# speaker_amp_single.net
KiCad netlist of a schematic drawn in EAGLE
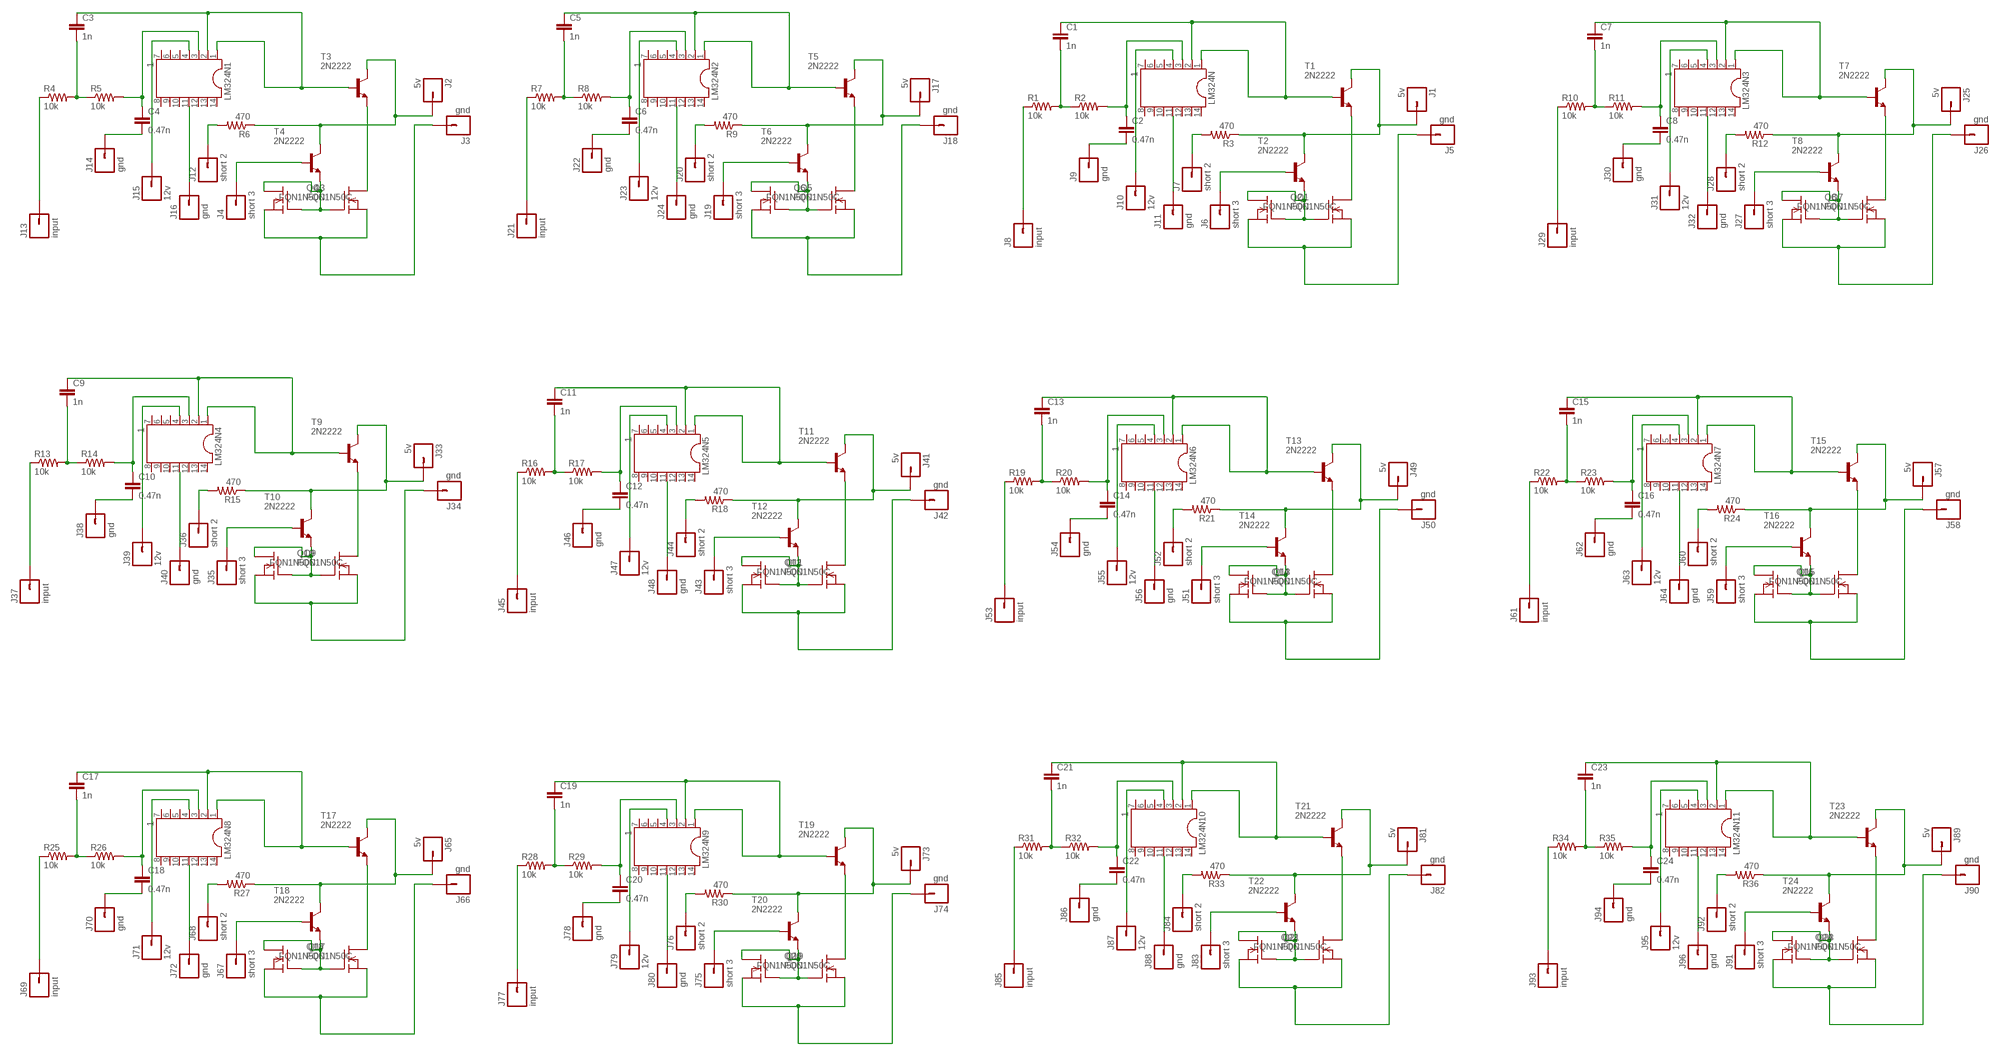
[diagram p0: schematic, sheet 1]

(export (version "E")
  (design (tool "Eeschema 10.0.6"))
  (components
    (comp (ref "C1")
      (value "1n")
      (footprint "eagle-import:CAP-PTH-SMALL")
      (libsource (lib "eagle-import") (part "CAPPTH"))
    )
    (comp (ref "C2")
      (value "0.47n")
      (footprint "eagle-import:CAP-PTH-SMALL")
      (libsource (lib "eagle-import") (part "CAPPTH"))
    )
    (comp (ref "C3")
      (value "1n")
      (footprint "eagle-import:CAP-PTH-SMALL")
      (libsource (lib "eagle-import") (part "CAPPTH"))
    )
    (comp (ref "C4")
      (value "0.47n")
      (footprint "eagle-import:CAP-PTH-SMALL")
      (libsource (lib "eagle-import") (part "CAPPTH"))
    )
    (comp (ref "C5")
      (value "1n")
      (footprint "eagle-import:CAP-PTH-SMALL")
      (libsource (lib "eagle-import") (part "CAPPTH"))
    )
    (comp (ref "C6")
      (value "0.47n")
      (footprint "eagle-import:CAP-PTH-SMALL")
      (libsource (lib "eagle-import") (part "CAPPTH"))
    )
    (comp (ref "C7")
      (value "1n")
      (footprint "eagle-import:CAP-PTH-SMALL")
      (libsource (lib "eagle-import") (part "CAPPTH"))
    )
    (comp (ref "C8")
      (value "0.47n")
      (footprint "eagle-import:CAP-PTH-SMALL")
      (libsource (lib "eagle-import") (part "CAPPTH"))
    )
    (comp (ref "C9")
      (value "1n")
      (footprint "eagle-import:CAP-PTH-SMALL")
      (libsource (lib "eagle-import") (part "CAPPTH"))
    )
    (comp (ref "C10")
      (value "0.47n")
      (footprint "eagle-import:CAP-PTH-SMALL")
      (libsource (lib "eagle-import") (part "CAPPTH"))
    )
    (comp (ref "C11")
      (value "1n")
      (footprint "eagle-import:CAP-PTH-SMALL")
      (libsource (lib "eagle-import") (part "CAPPTH"))
    )
    (comp (ref "C12")
      (value "0.47n")
      (footprint "eagle-import:CAP-PTH-SMALL")
      (libsource (lib "eagle-import") (part "CAPPTH"))
    )
    (comp (ref "C13")
      (value "1n")
      (footprint "eagle-import:CAP-PTH-SMALL")
      (libsource (lib "eagle-import") (part "CAPPTH"))
    )
    (comp (ref "C14")
      (value "0.47n")
      (footprint "eagle-import:CAP-PTH-SMALL")
      (libsource (lib "eagle-import") (part "CAPPTH"))
    )
    (comp (ref "C15")
      (value "1n")
      (footprint "eagle-import:CAP-PTH-SMALL")
      (libsource (lib "eagle-import") (part "CAPPTH"))
    )
    (comp (ref "C16")
      (value "0.47n")
      (footprint "eagle-import:CAP-PTH-SMALL")
      (libsource (lib "eagle-import") (part "CAPPTH"))
    )
    (comp (ref "C17")
      (value "1n")
      (footprint "eagle-import:CAP-PTH-SMALL")
      (libsource (lib "eagle-import") (part "CAPPTH"))
    )
    (comp (ref "C18")
      (value "0.47n")
      (footprint "eagle-import:CAP-PTH-SMALL")
      (libsource (lib "eagle-import") (part "CAPPTH"))
    )
    (comp (ref "C19")
      (value "1n")
      (footprint "eagle-import:CAP-PTH-SMALL")
      (libsource (lib "eagle-import") (part "CAPPTH"))
    )
    (comp (ref "C20")
      (value "0.47n")
      (footprint "eagle-import:CAP-PTH-SMALL")
      (libsource (lib "eagle-import") (part "CAPPTH"))
    )
    (comp (ref "C21")
      (value "1n")
      (footprint "eagle-import:CAP-PTH-SMALL")
      (libsource (lib "eagle-import") (part "CAPPTH"))
    )
    (comp (ref "C22")
      (value "0.47n")
      (footprint "eagle-import:CAP-PTH-SMALL")
      (libsource (lib "eagle-import") (part "CAPPTH"))
    )
    (comp (ref "C23")
      (value "1n")
      (footprint "eagle-import:CAP-PTH-SMALL")
      (libsource (lib "eagle-import") (part "CAPPTH"))
    )
    (comp (ref "C24")
      (value "0.47n")
      (footprint "eagle-import:CAP-PTH-SMALL")
      (libsource (lib "eagle-import") (part "CAPPTH"))
    )
    (comp (ref "J1")
      (value "5v")
      (footprint "eagle-import:1X01")
      (libsource (lib "eagle-import") (part "M01PTH"))
    )
    (comp (ref "J2")
      (value "5v")
      (footprint "eagle-import:1X01")
      (libsource (lib "eagle-import") (part "M01PTH"))
    )
    (comp (ref "J3")
      (value "gnd")
      (footprint "eagle-import:1X01")
      (libsource (lib "eagle-import") (part "M01PTH"))
    )
    (comp (ref "J4")
      (value "short 3")
      (footprint "eagle-import:1X01")
      (libsource (lib "eagle-import") (part "M01PTH"))
    )
    (comp (ref "J5")
      (value "gnd")
      (footprint "eagle-import:1X01")
      (libsource (lib "eagle-import") (part "M01PTH"))
    )
    (comp (ref "J6")
      (value "short 3")
      (footprint "eagle-import:1X01")
      (libsource (lib "eagle-import") (part "M01PTH"))
    )
    (comp (ref "J7")
      (value "short 2")
      (footprint "eagle-import:1X01")
      (libsource (lib "eagle-import") (part "M01PTH"))
    )
    (comp (ref "J8")
      (value "input")
      (footprint "eagle-import:1X01")
      (libsource (lib "eagle-import") (part "M01PTH"))
    )
    (comp (ref "J9")
      (value "gnd")
      (footprint "eagle-import:1X01")
      (libsource (lib "eagle-import") (part "M01PTH"))
    )
    (comp (ref "J10")
      (value "12v")
      (footprint "eagle-import:1X01")
      (libsource (lib "eagle-import") (part "M01PTH"))
    )
    (comp (ref "J11")
      (value "gnd")
      (footprint "eagle-import:1X01")
      (libsource (lib "eagle-import") (part "M01PTH"))
    )
    (comp (ref "J12")
      (value "short 2")
      (footprint "eagle-import:1X01")
      (libsource (lib "eagle-import") (part "M01PTH"))
    )
    (comp (ref "J13")
      (value "input")
      (footprint "eagle-import:1X01")
      (libsource (lib "eagle-import") (part "M01PTH"))
    )
    (comp (ref "J14")
      (value "gnd")
      (footprint "eagle-import:1X01")
      (libsource (lib "eagle-import") (part "M01PTH"))
    )
    (comp (ref "J15")
      (value "12v")
      (footprint "eagle-import:1X01")
      (libsource (lib "eagle-import") (part "M01PTH"))
    )
    (comp (ref "J16")
      (value "gnd")
      (footprint "eagle-import:1X01")
      (libsource (lib "eagle-import") (part "M01PTH"))
    )
    (comp (ref "J17")
      (value "5v")
      (footprint "eagle-import:1X01")
      (libsource (lib "eagle-import") (part "M01PTH"))
    )
    (comp (ref "J18")
      (value "gnd")
      (footprint "eagle-import:1X01")
      (libsource (lib "eagle-import") (part "M01PTH"))
    )
    (comp (ref "J19")
      (value "short 3")
      (footprint "eagle-import:1X01")
      (libsource (lib "eagle-import") (part "M01PTH"))
    )
    (comp (ref "J20")
      (value "short 2")
      (footprint "eagle-import:1X01")
      (libsource (lib "eagle-import") (part "M01PTH"))
    )
    (comp (ref "J21")
      (value "input")
      (footprint "eagle-import:1X01")
      (libsource (lib "eagle-import") (part "M01PTH"))
    )
    (comp (ref "J22")
      (value "gnd")
      (footprint "eagle-import:1X01")
      (libsource (lib "eagle-import") (part "M01PTH"))
    )
    (comp (ref "J23")
      (value "12v")
      (footprint "eagle-import:1X01")
      (libsource (lib "eagle-import") (part "M01PTH"))
    )
    (comp (ref "J24")
      (value "gnd")
      (footprint "eagle-import:1X01")
      (libsource (lib "eagle-import") (part "M01PTH"))
    )
    (comp (ref "J25")
      (value "5v")
      (footprint "eagle-import:1X01")
      (libsource (lib "eagle-import") (part "M01PTH"))
    )
    (comp (ref "J26")
      (value "gnd")
      (footprint "eagle-import:1X01")
      (libsource (lib "eagle-import") (part "M01PTH"))
    )
    (comp (ref "J27")
      (value "short 3")
      (footprint "eagle-import:1X01")
      (libsource (lib "eagle-import") (part "M01PTH"))
    )
    (comp (ref "J28")
      (value "short 2")
      (footprint "eagle-import:1X01")
      (libsource (lib "eagle-import") (part "M01PTH"))
    )
    (comp (ref "J29")
      (value "input")
      (footprint "eagle-import:1X01")
      (libsource (lib "eagle-import") (part "M01PTH"))
    )
    (comp (ref "J30")
      (value "gnd")
      (footprint "eagle-import:1X01")
      (libsource (lib "eagle-import") (part "M01PTH"))
    )
    (comp (ref "J31")
      (value "12v")
      (footprint "eagle-import:1X01")
      (libsource (lib "eagle-import") (part "M01PTH"))
    )
    (comp (ref "J32")
      (value "gnd")
      (footprint "eagle-import:1X01")
      (libsource (lib "eagle-import") (part "M01PTH"))
    )
    (comp (ref "J33")
      (value "5v")
      (footprint "eagle-import:1X01")
      (libsource (lib "eagle-import") (part "M01PTH"))
    )
    (comp (ref "J34")
      (value "gnd")
      (footprint "eagle-import:1X01")
      (libsource (lib "eagle-import") (part "M01PTH"))
    )
    (comp (ref "J35")
      (value "short 3")
      (footprint "eagle-import:1X01")
      (libsource (lib "eagle-import") (part "M01PTH"))
    )
    (comp (ref "J36")
      (value "short 2")
      (footprint "eagle-import:1X01")
      (libsource (lib "eagle-import") (part "M01PTH"))
    )
    (comp (ref "J37")
      (value "input")
      (footprint "eagle-import:1X01")
      (libsource (lib "eagle-import") (part "M01PTH"))
    )
    (comp (ref "J38")
      (value "gnd")
      (footprint "eagle-import:1X01")
      (libsource (lib "eagle-import") (part "M01PTH"))
    )
    (comp (ref "J39")
      (value "12v")
      (footprint "eagle-import:1X01")
      (libsource (lib "eagle-import") (part "M01PTH"))
    )
    (comp (ref "J40")
      (value "gnd")
      (footprint "eagle-import:1X01")
      (libsource (lib "eagle-import") (part "M01PTH"))
    )
    (comp (ref "J41")
      (value "5v")
      (footprint "eagle-import:1X01")
      (libsource (lib "eagle-import") (part "M01PTH"))
    )
    (comp (ref "J42")
      (value "gnd")
      (footprint "eagle-import:1X01")
      (libsource (lib "eagle-import") (part "M01PTH"))
    )
    (comp (ref "J43")
      (value "short 3")
      (footprint "eagle-import:1X01")
      (libsource (lib "eagle-import") (part "M01PTH"))
    )
    (comp (ref "J44")
      (value "short 2")
      (footprint "eagle-import:1X01")
      (libsource (lib "eagle-import") (part "M01PTH"))
    )
    (comp (ref "J45")
      (value "input")
      (footprint "eagle-import:1X01")
      (libsource (lib "eagle-import") (part "M01PTH"))
    )
    (comp (ref "J46")
      (value "gnd")
      (footprint "eagle-import:1X01")
      (libsource (lib "eagle-import") (part "M01PTH"))
    )
    (comp (ref "J47")
      (value "12v")
      (footprint "eagle-import:1X01")
      (libsource (lib "eagle-import") (part "M01PTH"))
    )
    (comp (ref "J48")
      (value "gnd")
      (footprint "eagle-import:1X01")
      (libsource (lib "eagle-import") (part "M01PTH"))
    )
    (comp (ref "J49")
      (value "5v")
      (footprint "eagle-import:1X01")
      (libsource (lib "eagle-import") (part "M01PTH"))
    )
    (comp (ref "J50")
      (value "gnd")
      (footprint "eagle-import:1X01")
      (libsource (lib "eagle-import") (part "M01PTH"))
    )
    (comp (ref "J51")
      (value "short 3")
      (footprint "eagle-import:1X01")
      (libsource (lib "eagle-import") (part "M01PTH"))
    )
    (comp (ref "J52")
      (value "short 2")
      (footprint "eagle-import:1X01")
      (libsource (lib "eagle-import") (part "M01PTH"))
    )
    (comp (ref "J53")
      (value "input")
      (footprint "eagle-import:1X01")
      (libsource (lib "eagle-import") (part "M01PTH"))
    )
    (comp (ref "J54")
      (value "gnd")
      (footprint "eagle-import:1X01")
      (libsource (lib "eagle-import") (part "M01PTH"))
    )
    (comp (ref "J55")
      (value "12v")
      (footprint "eagle-import:1X01")
      (libsource (lib "eagle-import") (part "M01PTH"))
    )
    (comp (ref "J56")
      (value "gnd")
      (footprint "eagle-import:1X01")
      (libsource (lib "eagle-import") (part "M01PTH"))
    )
    (comp (ref "J57")
      (value "5v")
      (footprint "eagle-import:1X01")
      (libsource (lib "eagle-import") (part "M01PTH"))
    )
    (comp (ref "J58")
      (value "gnd")
      (footprint "eagle-import:1X01")
      (libsource (lib "eagle-import") (part "M01PTH"))
    )
    (comp (ref "J59")
      (value "short 3")
      (footprint "eagle-import:1X01")
      (libsource (lib "eagle-import") (part "M01PTH"))
    )
    (comp (ref "J60")
      (value "short 2")
      (footprint "eagle-import:1X01")
      (libsource (lib "eagle-import") (part "M01PTH"))
    )
    (comp (ref "J61")
      (value "input")
      (footprint "eagle-import:1X01")
      (libsource (lib "eagle-import") (part "M01PTH"))
    )
    (comp (ref "J62")
      (value "gnd")
      (footprint "eagle-import:1X01")
      (libsource (lib "eagle-import") (part "M01PTH"))
    )
    (comp (ref "J63")
      (value "12v")
      (footprint "eagle-import:1X01")
      (libsource (lib "eagle-import") (part "M01PTH"))
    )
    (comp (ref "J64")
      (value "gnd")
      (footprint "eagle-import:1X01")
      (libsource (lib "eagle-import") (part "M01PTH"))
    )
    (comp (ref "J65")
      (value "5v")
      (footprint "eagle-import:1X01")
      (libsource (lib "eagle-import") (part "M01PTH"))
    )
    (comp (ref "J66")
      (value "gnd")
      (footprint "eagle-import:1X01")
      (libsource (lib "eagle-import") (part "M01PTH"))
    )
    (comp (ref "J67")
      (value "short 3")
      (footprint "eagle-import:1X01")
      (libsource (lib "eagle-import") (part "M01PTH"))
    )
    (comp (ref "J68")
      (value "short 2")
      (footprint "eagle-import:1X01")
      (libsource (lib "eagle-import") (part "M01PTH"))
    )
    (comp (ref "J69")
      (value "input")
      (footprint "eagle-import:1X01")
      (libsource (lib "eagle-import") (part "M01PTH"))
    )
    (comp (ref "J70")
      (value "gnd")
      (footprint "eagle-import:1X01")
      (libsource (lib "eagle-import") (part "M01PTH"))
    )
    (comp (ref "J71")
      (value "12v")
      (footprint "eagle-import:1X01")
      (libsource (lib "eagle-import") (part "M01PTH"))
    )
    (comp (ref "J72")
      (value "gnd")
      (footprint "eagle-import:1X01")
      (libsource (lib "eagle-import") (part "M01PTH"))
    )
    (comp (ref "J73")
      (value "5v")
      (footprint "eagle-import:1X01")
      (libsource (lib "eagle-import") (part "M01PTH"))
    )
    (comp (ref "J74")
      (value "gnd")
      (footprint "eagle-import:1X01")
      (libsource (lib "eagle-import") (part "M01PTH"))
    )
    (comp (ref "J75")
      (value "short 3")
      (footprint "eagle-import:1X01")
      (libsource (lib "eagle-import") (part "M01PTH"))
    )
    (comp (ref "J76")
      (value "short 2")
      (footprint "eagle-import:1X01")
      (libsource (lib "eagle-import") (part "M01PTH"))
    )
    (comp (ref "J77")
      (value "input")
      (footprint "eagle-import:1X01")
      (libsource (lib "eagle-import") (part "M01PTH"))
    )
    (comp (ref "J78")
      (value "gnd")
      (footprint "eagle-import:1X01")
      (libsource (lib "eagle-import") (part "M01PTH"))
    )
    (comp (ref "J79")
      (value "12v")
      (footprint "eagle-import:1X01")
      (libsource (lib "eagle-import") (part "M01PTH"))
    )
    (comp (ref "J80")
      (value "gnd")
      (footprint "eagle-import:1X01")
      (libsource (lib "eagle-import") (part "M01PTH"))
    )
    (comp (ref "J81")
      (value "5v")
      (footprint "eagle-import:1X01")
      (libsource (lib "eagle-import") (part "M01PTH"))
    )
    (comp (ref "J82")
      (value "gnd")
      (footprint "eagle-import:1X01")
      (libsource (lib "eagle-import") (part "M01PTH"))
    )
    (comp (ref "J83")
      (value "short 3")
      (footprint "eagle-import:1X01")
      (libsource (lib "eagle-import") (part "M01PTH"))
    )
    (comp (ref "J84")
      (value "short 2")
      (footprint "eagle-import:1X01")
      (libsource (lib "eagle-import") (part "M01PTH"))
    )
    (comp (ref "J85")
      (value "input")
      (footprint "eagle-import:1X01")
      (libsource (lib "eagle-import") (part "M01PTH"))
    )
    (comp (ref "J86")
      (value "gnd")
      (footprint "eagle-import:1X01")
      (libsource (lib "eagle-import") (part "M01PTH"))
    )
    (comp (ref "J87")
      (value "12v")
      (footprint "eagle-import:1X01")
      (libsource (lib "eagle-import") (part "M01PTH"))
    )
    (comp (ref "J88")
      (value "gnd")
      (footprint "eagle-import:1X01")
      (libsource (lib "eagle-import") (part "M01PTH"))
    )
    (comp (ref "J89")
      (value "5v")
      (footprint "eagle-import:1X01")
      (libsource (lib "eagle-import") (part "M01PTH"))
    )
    (comp (ref "J90")
      (value "gnd")
      (footprint "eagle-import:1X01")
      (libsource (lib "eagle-import") (part "M01PTH"))
    )
    (comp (ref "J91")
      (value "short 3")
      (footprint "eagle-import:1X01")
      (libsource (lib "eagle-import") (part "M01PTH"))
    )
    (comp (ref "J92")
      (value "short 2")
      (footprint "eagle-import:1X01")
      (libsource (lib "eagle-import") (part "M01PTH"))
    )
    (comp (ref "J93")
      (value "input")
      (footprint "eagle-import:1X01")
      (libsource (lib "eagle-import") (part "M01PTH"))
    )
    (comp (ref "J94")
      (value "gnd")
      (footprint "eagle-import:1X01")
      (libsource (lib "eagle-import") (part "M01PTH"))
    )
    (comp (ref "J95")
      (value "12v")
      (footprint "eagle-import:1X01")
      (libsource (lib "eagle-import") (part "M01PTH"))
    )
    (comp (ref "J96")
      (value "gnd")
      (footprint "eagle-import:1X01")
      (libsource (lib "eagle-import") (part "M01PTH"))
    )
    (comp (ref "LM324N")
      (value "1")
      (footprint "eagle-import:DIL14")
      (libsource (lib "eagle-import") (part "DIL14"))
    )
    (comp (ref "LM324N1")
      (value "1")
      (footprint "eagle-import:DIL14")
      (libsource (lib "eagle-import") (part "DIL14"))
    )
    (comp (ref "LM324N2")
      (value "1")
      (footprint "eagle-import:DIL14")
      (libsource (lib "eagle-import") (part "DIL14"))
    )
    (comp (ref "LM324N3")
      (value "1")
      (footprint "eagle-import:DIL14")
      (libsource (lib "eagle-import") (part "DIL14"))
    )
    (comp (ref "LM324N4")
      (value "1")
      (footprint "eagle-import:DIL14")
      (libsource (lib "eagle-import") (part "DIL14"))
    )
    (comp (ref "LM324N5")
      (value "1")
      (footprint "eagle-import:DIL14")
      (libsource (lib "eagle-import") (part "DIL14"))
    )
    (comp (ref "LM324N6")
      (value "1")
      (footprint "eagle-import:DIL14")
      (libsource (lib "eagle-import") (part "DIL14"))
    )
    (comp (ref "LM324N7")
      (value "1")
      (footprint "eagle-import:DIL14")
      (libsource (lib "eagle-import") (part "DIL14"))
    )
    (comp (ref "LM324N8")
      (value "1")
      (footprint "eagle-import:DIL14")
      (libsource (lib "eagle-import") (part "DIL14"))
    )
    (comp (ref "LM324N9")
      (value "1")
      (footprint "eagle-import:DIL14")
      (libsource (lib "eagle-import") (part "DIL14"))
    )
    (comp (ref "LM324N10")
      (value "1")
      (footprint "eagle-import:DIL14")
      (libsource (lib "eagle-import") (part "DIL14"))
    )
    (comp (ref "LM324N11")
      (value "1")
      (footprint "eagle-import:DIL14")
      (libsource (lib "eagle-import") (part "DIL14"))
    )
    (comp (ref "Q1")
      (value "FQN1N50C")
      (footprint "eagle-import:TO92")
      (libsource (lib "eagle-import") (part "FQN1N50C"))
    )
    (comp (ref "Q2")
      (value "FQN1N50C")
      (footprint "eagle-import:TO92")
      (libsource (lib "eagle-import") (part "FQN1N50C"))
    )
    (comp (ref "Q3")
      (value "FQN1N50C")
      (footprint "eagle-import:TO92")
      (libsource (lib "eagle-import") (part "FQN1N50C"))
    )
    (comp (ref "Q4")
      (value "FQN1N50C")
      (footprint "eagle-import:TO92")
      (libsource (lib "eagle-import") (part "FQN1N50C"))
    )
    (comp (ref "Q5")
      (value "FQN1N50C")
      (footprint "eagle-import:TO92")
      (libsource (lib "eagle-import") (part "FQN1N50C"))
    )
    (comp (ref "Q6")
      (value "FQN1N50C")
      (footprint "eagle-import:TO92")
      (libsource (lib "eagle-import") (part "FQN1N50C"))
    )
    (comp (ref "Q7")
      (value "FQN1N50C")
      (footprint "eagle-import:TO92")
      (libsource (lib "eagle-import") (part "FQN1N50C"))
    )
    (comp (ref "Q8")
      (value "FQN1N50C")
      (footprint "eagle-import:TO92")
      (libsource (lib "eagle-import") (part "FQN1N50C"))
    )
    (comp (ref "Q9")
      (value "FQN1N50C")
      (footprint "eagle-import:TO92")
      (libsource (lib "eagle-import") (part "FQN1N50C"))
    )
    (comp (ref "Q10")
      (value "FQN1N50C")
      (footprint "eagle-import:TO92")
      (libsource (lib "eagle-import") (part "FQN1N50C"))
    )
    (comp (ref "Q11")
      (value "FQN1N50C")
      (footprint "eagle-import:TO92")
      (libsource (lib "eagle-import") (part "FQN1N50C"))
    )
    (comp (ref "Q12")
      (value "FQN1N50C")
      (footprint "eagle-import:TO92")
      (libsource (lib "eagle-import") (part "FQN1N50C"))
    )
    (comp (ref "Q13")
      (value "FQN1N50C")
      (footprint "eagle-import:TO92")
      (libsource (lib "eagle-import") (part "FQN1N50C"))
    )
    (comp (ref "Q14")
      (value "FQN1N50C")
      (footprint "eagle-import:TO92")
      (libsource (lib "eagle-import") (part "FQN1N50C"))
    )
    (comp (ref "Q15")
      (value "FQN1N50C")
      (footprint "eagle-import:TO92")
      (libsource (lib "eagle-import") (part "FQN1N50C"))
    )
    (comp (ref "Q16")
      (value "FQN1N50C")
      (footprint "eagle-import:TO92")
      (libsource (lib "eagle-import") (part "FQN1N50C"))
    )
    (comp (ref "Q17")
      (value "FQN1N50C")
      (footprint "eagle-import:TO92")
      (libsource (lib "eagle-import") (part "FQN1N50C"))
    )
    (comp (ref "Q18")
      (value "FQN1N50C")
      (footprint "eagle-import:TO92")
      (libsource (lib "eagle-import") (part "FQN1N50C"))
    )
    (comp (ref "Q19")
      (value "FQN1N50C")
      (footprint "eagle-import:TO92")
      (libsource (lib "eagle-import") (part "FQN1N50C"))
    )
    (comp (ref "Q20")
      (value "FQN1N50C")
      (footprint "eagle-import:TO92")
      (libsource (lib "eagle-import") (part "FQN1N50C"))
    )
    (comp (ref "Q21")
      (value "FQN1N50C")
      (footprint "eagle-import:TO92")
      (libsource (lib "eagle-import") (part "FQN1N50C"))
    )
    (comp (ref "Q22")
      (value "FQN1N50C")
      (footprint "eagle-import:TO92")
      (libsource (lib "eagle-import") (part "FQN1N50C"))
    )
    (comp (ref "Q23")
      (value "FQN1N50C")
      (footprint "eagle-import:TO92")
      (libsource (lib "eagle-import") (part "FQN1N50C"))
    )
    (comp (ref "Q24")
      (value "FQN1N50C")
      (footprint "eagle-import:TO92")
      (libsource (lib "eagle-import") (part "FQN1N50C"))
    )
    (comp (ref "R1")
      (value "10k")
      (footprint "eagle-import:AXIAL-0.3")
      (libsource (lib "eagle-import") (part "RESISTORAXIAL-0.3"))
    )
    (comp (ref "R2")
      (value "10k")
      (footprint "eagle-import:AXIAL-0.3")
      (libsource (lib "eagle-import") (part "RESISTORAXIAL-0.3"))
    )
    (comp (ref "R3")
      (value "470")
      (footprint "eagle-import:AXIAL-0.3")
      (libsource (lib "eagle-import") (part "RESISTORAXIAL-0.3"))
    )
    (comp (ref "R4")
      (value "10k")
      (footprint "eagle-import:AXIAL-0.3")
      (libsource (lib "eagle-import") (part "RESISTORAXIAL-0.3"))
    )
    (comp (ref "R5")
      (value "10k")
      (footprint "eagle-import:AXIAL-0.3")
      (libsource (lib "eagle-import") (part "RESISTORAXIAL-0.3"))
    )
    (comp (ref "R6")
      (value "470")
      (footprint "eagle-import:AXIAL-0.3")
      (libsource (lib "eagle-import") (part "RESISTORAXIAL-0.3"))
    )
    (comp (ref "R7")
      (value "10k")
      (footprint "eagle-import:AXIAL-0.3")
      (libsource (lib "eagle-import") (part "RESISTORAXIAL-0.3"))
    )
    (comp (ref "R8")
      (value "10k")
      (footprint "eagle-import:AXIAL-0.3")
      (libsource (lib "eagle-import") (part "RESISTORAXIAL-0.3"))
    )
    (comp (ref "R9")
      (value "470")
      (footprint "eagle-import:AXIAL-0.3")
      (libsource (lib "eagle-import") (part "RESISTORAXIAL-0.3"))
    )
    (comp (ref "R10")
      (value "10k")
      (footprint "eagle-import:AXIAL-0.3")
      (libsource (lib "eagle-import") (part "RESISTORAXIAL-0.3"))
    )
    (comp (ref "R11")
      (value "10k")
      (footprint "eagle-import:AXIAL-0.3")
      (libsource (lib "eagle-import") (part "RESISTORAXIAL-0.3"))
    )
    (comp (ref "R12")
      (value "470")
      (footprint "eagle-import:AXIAL-0.3")
      (libsource (lib "eagle-import") (part "RESISTORAXIAL-0.3"))
    )
    (comp (ref "R13")
      (value "10k")
      (footprint "eagle-import:AXIAL-0.3")
      (libsource (lib "eagle-import") (part "RESISTORAXIAL-0.3"))
    )
    (comp (ref "R14")
      (value "10k")
      (footprint "eagle-import:AXIAL-0.3")
      (libsource (lib "eagle-import") (part "RESISTORAXIAL-0.3"))
    )
    (comp (ref "R15")
      (value "470")
      (footprint "eagle-import:AXIAL-0.3")
      (libsource (lib "eagle-import") (part "RESISTORAXIAL-0.3"))
    )
    (comp (ref "R16")
      (value "10k")
      (footprint "eagle-import:AXIAL-0.3")
      (libsource (lib "eagle-import") (part "RESISTORAXIAL-0.3"))
    )
    (comp (ref "R17")
      (value "10k")
      (footprint "eagle-import:AXIAL-0.3")
      (libsource (lib "eagle-import") (part "RESISTORAXIAL-0.3"))
    )
    (comp (ref "R18")
      (value "470")
      (footprint "eagle-import:AXIAL-0.3")
      (libsource (lib "eagle-import") (part "RESISTORAXIAL-0.3"))
    )
    (comp (ref "R19")
      (value "10k")
      (footprint "eagle-import:AXIAL-0.3")
      (libsource (lib "eagle-import") (part "RESISTORAXIAL-0.3"))
    )
    (comp (ref "R20")
      (value "10k")
      (footprint "eagle-import:AXIAL-0.3")
      (libsource (lib "eagle-import") (part "RESISTORAXIAL-0.3"))
    )
    (comp (ref "R21")
      (value "470")
      (footprint "eagle-import:AXIAL-0.3")
      (libsource (lib "eagle-import") (part "RESISTORAXIAL-0.3"))
    )
    (comp (ref "R22")
      (value "10k")
      (footprint "eagle-import:AXIAL-0.3")
      (libsource (lib "eagle-import") (part "RESISTORAXIAL-0.3"))
    )
    (comp (ref "R23")
      (value "10k")
      (footprint "eagle-import:AXIAL-0.3")
      (libsource (lib "eagle-import") (part "RESISTORAXIAL-0.3"))
    )
    (comp (ref "R24")
      (value "470")
      (footprint "eagle-import:AXIAL-0.3")
      (libsource (lib "eagle-import") (part "RESISTORAXIAL-0.3"))
    )
    (comp (ref "R25")
      (value "10k")
      (footprint "eagle-import:AXIAL-0.3")
      (libsource (lib "eagle-import") (part "RESISTORAXIAL-0.3"))
    )
    (comp (ref "R26")
      (value "10k")
      (footprint "eagle-import:AXIAL-0.3")
      (libsource (lib "eagle-import") (part "RESISTORAXIAL-0.3"))
    )
    (comp (ref "R27")
      (value "470")
      (footprint "eagle-import:AXIAL-0.3")
      (libsource (lib "eagle-import") (part "RESISTORAXIAL-0.3"))
    )
    (comp (ref "R28")
      (value "10k")
      (footprint "eagle-import:AXIAL-0.3")
      (libsource (lib "eagle-import") (part "RESISTORAXIAL-0.3"))
    )
    (comp (ref "R29")
      (value "10k")
      (footprint "eagle-import:AXIAL-0.3")
      (libsource (lib "eagle-import") (part "RESISTORAXIAL-0.3"))
    )
    (comp (ref "R30")
      (value "470")
      (footprint "eagle-import:AXIAL-0.3")
      (libsource (lib "eagle-import") (part "RESISTORAXIAL-0.3"))
    )
    (comp (ref "R31")
      (value "10k")
      (footprint "eagle-import:AXIAL-0.3")
      (libsource (lib "eagle-import") (part "RESISTORAXIAL-0.3"))
    )
    (comp (ref "R32")
      (value "10k")
      (footprint "eagle-import:AXIAL-0.3")
      (libsource (lib "eagle-import") (part "RESISTORAXIAL-0.3"))
    )
    (comp (ref "R33")
      (value "470")
      (footprint "eagle-import:AXIAL-0.3")
      (libsource (lib "eagle-import") (part "RESISTORAXIAL-0.3"))
    )
    (comp (ref "R34")
      (value "10k")
      (footprint "eagle-import:AXIAL-0.3")
      (libsource (lib "eagle-import") (part "RESISTORAXIAL-0.3"))
    )
    (comp (ref "R35")
      (value "10k")
      (footprint "eagle-import:AXIAL-0.3")
      (libsource (lib "eagle-import") (part "RESISTORAXIAL-0.3"))
    )
    (comp (ref "R36")
      (value "470")
      (footprint "eagle-import:AXIAL-0.3")
      (libsource (lib "eagle-import") (part "RESISTORAXIAL-0.3"))
    )
    (comp (ref "T1")
      (value "2N2222")
      (footprint "eagle-import:TO92-EBC-OVAL")
      (libsource (lib "eagle-import") (part "2N2222"))
    )
    (comp (ref "T2")
      (value "2N2222")
      (footprint "eagle-import:TO92-EBC-OVAL")
      (libsource (lib "eagle-import") (part "2N2222"))
    )
    (comp (ref "T3")
      (value "2N2222")
      (footprint "eagle-import:TO92-EBC-OVAL")
      (libsource (lib "eagle-import") (part "2N2222"))
    )
    (comp (ref "T4")
      (value "2N2222")
      (footprint "eagle-import:TO92-EBC-OVAL")
      (libsource (lib "eagle-import") (part "2N2222"))
    )
    (comp (ref "T5")
      (value "2N2222")
      (footprint "eagle-import:TO92-EBC-OVAL")
      (libsource (lib "eagle-import") (part "2N2222"))
    )
    (comp (ref "T6")
      (value "2N2222")
      (footprint "eagle-import:TO92-EBC-OVAL")
      (libsource (lib "eagle-import") (part "2N2222"))
    )
    (comp (ref "T7")
      (value "2N2222")
      (footprint "eagle-import:TO92-EBC-OVAL")
      (libsource (lib "eagle-import") (part "2N2222"))
    )
    (comp (ref "T8")
      (value "2N2222")
      (footprint "eagle-import:TO92-EBC-OVAL")
      (libsource (lib "eagle-import") (part "2N2222"))
    )
    (comp (ref "T9")
      (value "2N2222")
      (footprint "eagle-import:TO92-EBC-OVAL")
      (libsource (lib "eagle-import") (part "2N2222"))
    )
    (comp (ref "T10")
      (value "2N2222")
      (footprint "eagle-import:TO92-EBC-OVAL")
      (libsource (lib "eagle-import") (part "2N2222"))
    )
    (comp (ref "T11")
      (value "2N2222")
      (footprint "eagle-import:TO92-EBC-OVAL")
      (libsource (lib "eagle-import") (part "2N2222"))
    )
    (comp (ref "T12")
      (value "2N2222")
      (footprint "eagle-import:TO92-EBC-OVAL")
      (libsource (lib "eagle-import") (part "2N2222"))
    )
    (comp (ref "T13")
      (value "2N2222")
      (footprint "eagle-import:TO92-EBC-OVAL")
      (libsource (lib "eagle-import") (part "2N2222"))
    )
    (comp (ref "T14")
      (value "2N2222")
      (footprint "eagle-import:TO92-EBC-OVAL")
      (libsource (lib "eagle-import") (part "2N2222"))
    )
    (comp (ref "T15")
      (value "2N2222")
      (footprint "eagle-import:TO92-EBC-OVAL")
      (libsource (lib "eagle-import") (part "2N2222"))
    )
    (comp (ref "T16")
      (value "2N2222")
      (footprint "eagle-import:TO92-EBC-OVAL")
      (libsource (lib "eagle-import") (part "2N2222"))
    )
    (comp (ref "T17")
      (value "2N2222")
      (footprint "eagle-import:TO92-EBC-OVAL")
      (libsource (lib "eagle-import") (part "2N2222"))
    )
    (comp (ref "T18")
      (value "2N2222")
      (footprint "eagle-import:TO92-EBC-OVAL")
      (libsource (lib "eagle-import") (part "2N2222"))
    )
    (comp (ref "T19")
      (value "2N2222")
      (footprint "eagle-import:TO92-EBC-OVAL")
      (libsource (lib "eagle-import") (part "2N2222"))
    )
    (comp (ref "T20")
      (value "2N2222")
      (footprint "eagle-import:TO92-EBC-OVAL")
      (libsource (lib "eagle-import") (part "2N2222"))
    )
    (comp (ref "T21")
      (value "2N2222")
      (footprint "eagle-import:TO92-EBC-OVAL")
      (libsource (lib "eagle-import") (part "2N2222"))
    )
    (comp (ref "T22")
      (value "2N2222")
      (footprint "eagle-import:TO92-EBC-OVAL")
      (libsource (lib "eagle-import") (part "2N2222"))
    )
    (comp (ref "T23")
      (value "2N2222")
      (footprint "eagle-import:TO92-EBC-OVAL")
      (libsource (lib "eagle-import") (part "2N2222"))
    )
    (comp (ref "T24")
      (value "2N2222")
      (footprint "eagle-import:TO92-EBC-OVAL")
      (libsource (lib "eagle-import") (part "2N2222"))
    )
  )
  (nets
    (net (code "1") (name "Net-(C1-Pad1)") (class "Default")
      (node (ref "C1") (pin "1") (pinfunction "1_1") (pintype "passive"))
      (node (ref "LM324N") (pin "1") (pinfunction "1_1") (pintype "passive"))
      (node (ref "LM324N") (pin "2") (pinfunction "2_2") (pintype "passive"))
      (node (ref "T1") (pin "B") (pinfunction "B_B") (pintype "passive"))
    )
    (net (code "2") (name "Net-(C2-Pad2)") (class "Default")
      (node (ref "C2") (pin "2") (pinfunction "2_2") (pintype "passive"))
      (node (ref "J9") (pin "1") (pinfunction "1_1") (pintype "passive"))
    )
    (net (code "3") (name "Net-(C3-Pad1)") (class "Default")
      (node (ref "C3") (pin "1") (pinfunction "1_1") (pintype "passive"))
      (node (ref "LM324N1") (pin "1") (pinfunction "1_1") (pintype "passive"))
      (node (ref "LM324N1") (pin "2") (pinfunction "2_2") (pintype "passive"))
      (node (ref "T3") (pin "B") (pinfunction "B_B") (pintype "passive"))
    )
    (net (code "4") (name "Net-(C4-Pad2)") (class "Default")
      (node (ref "C4") (pin "2") (pinfunction "2_2") (pintype "passive"))
      (node (ref "J14") (pin "1") (pinfunction "1_1") (pintype "passive"))
    )
    (net (code "5") (name "Net-(C5-Pad1)") (class "Default")
      (node (ref "C5") (pin "1") (pinfunction "1_1") (pintype "passive"))
      (node (ref "LM324N2") (pin "1") (pinfunction "1_1") (pintype "passive"))
      (node (ref "LM324N2") (pin "2") (pinfunction "2_2") (pintype "passive"))
      (node (ref "T5") (pin "B") (pinfunction "B_B") (pintype "passive"))
    )
    (net (code "6") (name "Net-(C6-Pad2)") (class "Default")
      (node (ref "C6") (pin "2") (pinfunction "2_2") (pintype "passive"))
      (node (ref "J22") (pin "1") (pinfunction "1_1") (pintype "passive"))
    )
    (net (code "7") (name "Net-(C7-Pad1)") (class "Default")
      (node (ref "C7") (pin "1") (pinfunction "1_1") (pintype "passive"))
      (node (ref "LM324N3") (pin "1") (pinfunction "1_1") (pintype "passive"))
      (node (ref "LM324N3") (pin "2") (pinfunction "2_2") (pintype "passive"))
      (node (ref "T7") (pin "B") (pinfunction "B_B") (pintype "passive"))
    )
    (net (code "8") (name "Net-(C8-Pad2)") (class "Default")
      (node (ref "C8") (pin "2") (pinfunction "2_2") (pintype "passive"))
      (node (ref "J30") (pin "1") (pinfunction "1_1") (pintype "passive"))
    )
    (net (code "9") (name "Net-(C9-Pad1)") (class "Default")
      (node (ref "C9") (pin "1") (pinfunction "1_1") (pintype "passive"))
      (node (ref "LM324N4") (pin "1") (pinfunction "1_1") (pintype "passive"))
      (node (ref "LM324N4") (pin "2") (pinfunction "2_2") (pintype "passive"))
      (node (ref "T9") (pin "B") (pinfunction "B_B") (pintype "passive"))
    )
    (net (code "10") (name "Net-(C10-Pad2)") (class "Default")
      (node (ref "C10") (pin "2") (pinfunction "2_2") (pintype "passive"))
      (node (ref "J38") (pin "1") (pinfunction "1_1") (pintype "passive"))
    )
    (net (code "11") (name "Net-(C11-Pad1)") (class "Default")
      (node (ref "C11") (pin "1") (pinfunction "1_1") (pintype "passive"))
      (node (ref "LM324N5") (pin "1") (pinfunction "1_1") (pintype "passive"))
      (node (ref "LM324N5") (pin "2") (pinfunction "2_2") (pintype "passive"))
      (node (ref "T11") (pin "B") (pinfunction "B_B") (pintype "passive"))
    )
    (net (code "12") (name "Net-(C12-Pad2)") (class "Default")
      (node (ref "C12") (pin "2") (pinfunction "2_2") (pintype "passive"))
      (node (ref "J46") (pin "1") (pinfunction "1_1") (pintype "passive"))
    )
    (net (code "13") (name "Net-(C13-Pad1)") (class "Default")
      (node (ref "C13") (pin "1") (pinfunction "1_1") (pintype "passive"))
      (node (ref "LM324N6") (pin "1") (pinfunction "1_1") (pintype "passive"))
      (node (ref "LM324N6") (pin "2") (pinfunction "2_2") (pintype "passive"))
      (node (ref "T13") (pin "B") (pinfunction "B_B") (pintype "passive"))
    )
    (net (code "14") (name "Net-(C14-Pad2)") (class "Default")
      (node (ref "C14") (pin "2") (pinfunction "2_2") (pintype "passive"))
      (node (ref "J54") (pin "1") (pinfunction "1_1") (pintype "passive"))
    )
    (net (code "15") (name "Net-(C15-Pad1)") (class "Default")
      (node (ref "C15") (pin "1") (pinfunction "1_1") (pintype "passive"))
      (node (ref "LM324N7") (pin "1") (pinfunction "1_1") (pintype "passive"))
      (node (ref "LM324N7") (pin "2") (pinfunction "2_2") (pintype "passive"))
      (node (ref "T15") (pin "B") (pinfunction "B_B") (pintype "passive"))
    )
    (net (code "16") (name "Net-(C16-Pad2)") (class "Default")
      (node (ref "C16") (pin "2") (pinfunction "2_2") (pintype "passive"))
      (node (ref "J62") (pin "1") (pinfunction "1_1") (pintype "passive"))
    )
    (net (code "17") (name "Net-(C17-Pad1)") (class "Default")
      (node (ref "C17") (pin "1") (pinfunction "1_1") (pintype "passive"))
      (node (ref "LM324N8") (pin "1") (pinfunction "1_1") (pintype "passive"))
      (node (ref "LM324N8") (pin "2") (pinfunction "2_2") (pintype "passive"))
      (node (ref "T17") (pin "B") (pinfunction "B_B") (pintype "passive"))
    )
    (net (code "18") (name "Net-(C18-Pad2)") (class "Default")
      (node (ref "C18") (pin "2") (pinfunction "2_2") (pintype "passive"))
      (node (ref "J70") (pin "1") (pinfunction "1_1") (pintype "passive"))
    )
    (net (code "19") (name "Net-(C19-Pad1)") (class "Default")
      (node (ref "C19") (pin "1") (pinfunction "1_1") (pintype "passive"))
      (node (ref "LM324N9") (pin "1") (pinfunction "1_1") (pintype "passive"))
      (node (ref "LM324N9") (pin "2") (pinfunction "2_2") (pintype "passive"))
      (node (ref "T19") (pin "B") (pinfunction "B_B") (pintype "passive"))
    )
    (net (code "20") (name "Net-(C20-Pad2)") (class "Default")
      (node (ref "C20") (pin "2") (pinfunction "2_2") (pintype "passive"))
      (node (ref "J78") (pin "1") (pinfunction "1_1") (pintype "passive"))
    )
    (net (code "21") (name "Net-(C21-Pad1)") (class "Default")
      (node (ref "C21") (pin "1") (pinfunction "1_1") (pintype "passive"))
      (node (ref "LM324N10") (pin "1") (pinfunction "1_1") (pintype "passive"))
      (node (ref "LM324N10") (pin "2") (pinfunction "2_2") (pintype "passive"))
      (node (ref "T21") (pin "B") (pinfunction "B_B") (pintype "passive"))
    )
    (net (code "22") (name "Net-(C22-Pad2)") (class "Default")
      (node (ref "C22") (pin "2") (pinfunction "2_2") (pintype "passive"))
      (node (ref "J86") (pin "1") (pinfunction "1_1") (pintype "passive"))
    )
    (net (code "23") (name "Net-(C23-Pad1)") (class "Default")
      (node (ref "C23") (pin "1") (pinfunction "1_1") (pintype "passive"))
      (node (ref "LM324N11") (pin "1") (pinfunction "1_1") (pintype "passive"))
      (node (ref "LM324N11") (pin "2") (pinfunction "2_2") (pintype "passive"))
      (node (ref "T23") (pin "B") (pinfunction "B_B") (pintype "passive"))
    )
    (net (code "24") (name "Net-(C24-Pad2)") (class "Default")
      (node (ref "C24") (pin "2") (pinfunction "2_2") (pintype "passive"))
      (node (ref "J94") (pin "1") (pinfunction "1_1") (pintype "passive"))
    )
    (net (code "25") (name "Net-(J4-Pad1)") (class "Default")
      (node (ref "J4") (pin "1") (pinfunction "1_1") (pintype "passive"))
      (node (ref "T4") (pin "B") (pinfunction "B_B") (pintype "passive"))
    )
    (net (code "26") (name "Net-(J6-Pad1)") (class "Default")
      (node (ref "J6") (pin "1") (pinfunction "1_1") (pintype "passive"))
      (node (ref "T2") (pin "B") (pinfunction "B_B") (pintype "passive"))
    )
    (net (code "27") (name "Net-(J10-Pad1)") (class "Default")
      (node (ref "J10") (pin "1") (pinfunction "1_1") (pintype "passive"))
      (node (ref "LM324N") (pin "4") (pinfunction "4_4") (pintype "passive"))
    )
    (net (code "28") (name "Net-(J11-Pad1)") (class "Default")
      (node (ref "J11") (pin "1") (pinfunction "1_1") (pintype "passive"))
      (node (ref "LM324N") (pin "11") (pinfunction "11_11") (pintype "passive"))
    )
    (net (code "29") (name "Net-(J15-Pad1)") (class "Default")
      (node (ref "J15") (pin "1") (pinfunction "1_1") (pintype "passive"))
      (node (ref "LM324N1") (pin "4") (pinfunction "4_4") (pintype "passive"))
    )
    (net (code "30") (name "Net-(J16-Pad1)") (class "Default")
      (node (ref "J16") (pin "1") (pinfunction "1_1") (pintype "passive"))
      (node (ref "LM324N1") (pin "11") (pinfunction "11_11") (pintype "passive"))
    )
    (net (code "31") (name "Net-(J19-Pad1)") (class "Default")
      (node (ref "J19") (pin "1") (pinfunction "1_1") (pintype "passive"))
      (node (ref "T6") (pin "B") (pinfunction "B_B") (pintype "passive"))
    )
    (net (code "32") (name "Net-(J23-Pad1)") (class "Default")
      (node (ref "J23") (pin "1") (pinfunction "1_1") (pintype "passive"))
      (node (ref "LM324N2") (pin "4") (pinfunction "4_4") (pintype "passive"))
    )
    (net (code "33") (name "Net-(J24-Pad1)") (class "Default")
      (node (ref "J24") (pin "1") (pinfunction "1_1") (pintype "passive"))
      (node (ref "LM324N2") (pin "11") (pinfunction "11_11") (pintype "passive"))
    )
    (net (code "34") (name "Net-(J27-Pad1)") (class "Default")
      (node (ref "J27") (pin "1") (pinfunction "1_1") (pintype "passive"))
      (node (ref "T8") (pin "B") (pinfunction "B_B") (pintype "passive"))
    )
    (net (code "35") (name "Net-(J31-Pad1)") (class "Default")
      (node (ref "J31") (pin "1") (pinfunction "1_1") (pintype "passive"))
      (node (ref "LM324N3") (pin "4") (pinfunction "4_4") (pintype "passive"))
    )
    (net (code "36") (name "Net-(J32-Pad1)") (class "Default")
      (node (ref "J32") (pin "1") (pinfunction "1_1") (pintype "passive"))
      (node (ref "LM324N3") (pin "11") (pinfunction "11_11") (pintype "passive"))
    )
    (net (code "37") (name "Net-(J35-Pad1)") (class "Default")
      (node (ref "J35") (pin "1") (pinfunction "1_1") (pintype "passive"))
      (node (ref "T10") (pin "B") (pinfunction "B_B") (pintype "passive"))
    )
    (net (code "38") (name "Net-(J39-Pad1)") (class "Default")
      (node (ref "J39") (pin "1") (pinfunction "1_1") (pintype "passive"))
      (node (ref "LM324N4") (pin "4") (pinfunction "4_4") (pintype "passive"))
    )
    (net (code "39") (name "Net-(J40-Pad1)") (class "Default")
      (node (ref "J40") (pin "1") (pinfunction "1_1") (pintype "passive"))
      (node (ref "LM324N4") (pin "11") (pinfunction "11_11") (pintype "passive"))
    )
    (net (code "40") (name "Net-(J43-Pad1)") (class "Default")
      (node (ref "J43") (pin "1") (pinfunction "1_1") (pintype "passive"))
      (node (ref "T12") (pin "B") (pinfunction "B_B") (pintype "passive"))
    )
    (net (code "41") (name "Net-(J47-Pad1)") (class "Default")
      (node (ref "J47") (pin "1") (pinfunction "1_1") (pintype "passive"))
      (node (ref "LM324N5") (pin "4") (pinfunction "4_4") (pintype "passive"))
    )
    (net (code "42") (name "Net-(J48-Pad1)") (class "Default")
      (node (ref "J48") (pin "1") (pinfunction "1_1") (pintype "passive"))
      (node (ref "LM324N5") (pin "11") (pinfunction "11_11") (pintype "passive"))
    )
    (net (code "43") (name "Net-(J51-Pad1)") (class "Default")
      (node (ref "J51") (pin "1") (pinfunction "1_1") (pintype "passive"))
      (node (ref "T14") (pin "B") (pinfunction "B_B") (pintype "passive"))
    )
    (net (code "44") (name "Net-(J55-Pad1)") (class "Default")
      (node (ref "J55") (pin "1") (pinfunction "1_1") (pintype "passive"))
      (node (ref "LM324N6") (pin "4") (pinfunction "4_4") (pintype "passive"))
    )
    (net (code "45") (name "Net-(J56-Pad1)") (class "Default")
      (node (ref "J56") (pin "1") (pinfunction "1_1") (pintype "passive"))
      (node (ref "LM324N6") (pin "11") (pinfunction "11_11") (pintype "passive"))
    )
    (net (code "46") (name "Net-(J59-Pad1)") (class "Default")
      (node (ref "J59") (pin "1") (pinfunction "1_1") (pintype "passive"))
      (node (ref "T16") (pin "B") (pinfunction "B_B") (pintype "passive"))
    )
    (net (code "47") (name "Net-(J63-Pad1)") (class "Default")
      (node (ref "J63") (pin "1") (pinfunction "1_1") (pintype "passive"))
      (node (ref "LM324N7") (pin "4") (pinfunction "4_4") (pintype "passive"))
    )
    (net (code "48") (name "Net-(J64-Pad1)") (class "Default")
      (node (ref "J64") (pin "1") (pinfunction "1_1") (pintype "passive"))
      (node (ref "LM324N7") (pin "11") (pinfunction "11_11") (pintype "passive"))
    )
    (net (code "49") (name "Net-(J67-Pad1)") (class "Default")
      (node (ref "J67") (pin "1") (pinfunction "1_1") (pintype "passive"))
      (node (ref "T18") (pin "B") (pinfunction "B_B") (pintype "passive"))
    )
    (net (code "50") (name "Net-(J71-Pad1)") (class "Default")
      (node (ref "J71") (pin "1") (pinfunction "1_1") (pintype "passive"))
      (node (ref "LM324N8") (pin "4") (pinfunction "4_4") (pintype "passive"))
    )
    (net (code "51") (name "Net-(J72-Pad1)") (class "Default")
      (node (ref "J72") (pin "1") (pinfunction "1_1") (pintype "passive"))
      (node (ref "LM324N8") (pin "11") (pinfunction "11_11") (pintype "passive"))
    )
    (net (code "52") (name "Net-(J75-Pad1)") (class "Default")
      (node (ref "J75") (pin "1") (pinfunction "1_1") (pintype "passive"))
      (node (ref "T20") (pin "B") (pinfunction "B_B") (pintype "passive"))
    )
    (net (code "53") (name "Net-(J79-Pad1)") (class "Default")
      (node (ref "J79") (pin "1") (pinfunction "1_1") (pintype "passive"))
      (node (ref "LM324N9") (pin "4") (pinfunction "4_4") (pintype "passive"))
    )
    (net (code "54") (name "Net-(J80-Pad1)") (class "Default")
      (node (ref "J80") (pin "1") (pinfunction "1_1") (pintype "passive"))
      (node (ref "LM324N9") (pin "11") (pinfunction "11_11") (pintype "passive"))
    )
    (net (code "55") (name "Net-(J83-Pad1)") (class "Default")
      (node (ref "J83") (pin "1") (pinfunction "1_1") (pintype "passive"))
      (node (ref "T22") (pin "B") (pinfunction "B_B") (pintype "passive"))
    )
    (net (code "56") (name "Net-(J87-Pad1)") (class "Default")
      (node (ref "J87") (pin "1") (pinfunction "1_1") (pintype "passive"))
      (node (ref "LM324N10") (pin "4") (pinfunction "4_4") (pintype "passive"))
    )
    (net (code "57") (name "Net-(J88-Pad1)") (class "Default")
      (node (ref "J88") (pin "1") (pinfunction "1_1") (pintype "passive"))
      (node (ref "LM324N10") (pin "11") (pinfunction "11_11") (pintype "passive"))
    )
    (net (code "58") (name "Net-(J91-Pad1)") (class "Default")
      (node (ref "J91") (pin "1") (pinfunction "1_1") (pintype "passive"))
      (node (ref "T24") (pin "B") (pinfunction "B_B") (pintype "passive"))
    )
    (net (code "59") (name "Net-(J95-Pad1)") (class "Default")
      (node (ref "J95") (pin "1") (pinfunction "1_1") (pintype "passive"))
      (node (ref "LM324N11") (pin "4") (pinfunction "4_4") (pintype "passive"))
    )
    (net (code "60") (name "Net-(J96-Pad1)") (class "Default")
      (node (ref "J96") (pin "1") (pinfunction "1_1") (pintype "passive"))
      (node (ref "LM324N11") (pin "11") (pinfunction "11_11") (pintype "passive"))
    )
    (net (code "61") (name "Net-(Q1-D)") (class "Default")
      (node (ref "Q1") (pin "1") (pinfunction "G_1") (pintype "passive"))
      (node (ref "Q1") (pin "2") (pinfunction "D_2") (pintype "passive"))
      (node (ref "Q2") (pin "1") (pinfunction "G_1") (pintype "passive"))
      (node (ref "T2") (pin "E") (pinfunction "E_E") (pintype "passive"))
    )
    (net (code "62") (name "Net-(Q1-S)") (class "Default")
      (node (ref "J5") (pin "1") (pinfunction "1_1") (pintype "passive"))
      (node (ref "Q1") (pin "3") (pinfunction "S_3") (pintype "passive"))
      (node (ref "Q2") (pin "3") (pinfunction "S_3") (pintype "passive"))
    )
    (net (code "63") (name "Net-(Q2-D)") (class "Default")
      (node (ref "Q2") (pin "2") (pinfunction "D_2") (pintype "passive"))
      (node (ref "T1") (pin "E") (pinfunction "E_E") (pintype "passive"))
    )
    (net (code "64") (name "Net-(Q3-D)") (class "Default")
      (node (ref "Q3") (pin "1") (pinfunction "G_1") (pintype "passive"))
      (node (ref "Q3") (pin "2") (pinfunction "D_2") (pintype "passive"))
      (node (ref "Q4") (pin "1") (pinfunction "G_1") (pintype "passive"))
      (node (ref "T4") (pin "E") (pinfunction "E_E") (pintype "passive"))
    )
    (net (code "65") (name "Net-(Q3-S)") (class "Default")
      (node (ref "J3") (pin "1") (pinfunction "1_1") (pintype "passive"))
      (node (ref "Q3") (pin "3") (pinfunction "S_3") (pintype "passive"))
      (node (ref "Q4") (pin "3") (pinfunction "S_3") (pintype "passive"))
    )
    (net (code "66") (name "Net-(Q4-D)") (class "Default")
      (node (ref "Q4") (pin "2") (pinfunction "D_2") (pintype "passive"))
      (node (ref "T3") (pin "E") (pinfunction "E_E") (pintype "passive"))
    )
    (net (code "67") (name "Net-(Q5-D)") (class "Default")
      (node (ref "Q5") (pin "1") (pinfunction "G_1") (pintype "passive"))
      (node (ref "Q5") (pin "2") (pinfunction "D_2") (pintype "passive"))
      (node (ref "Q6") (pin "1") (pinfunction "G_1") (pintype "passive"))
      (node (ref "T6") (pin "E") (pinfunction "E_E") (pintype "passive"))
    )
    (net (code "68") (name "Net-(Q5-S)") (class "Default")
      (node (ref "J18") (pin "1") (pinfunction "1_1") (pintype "passive"))
      (node (ref "Q5") (pin "3") (pinfunction "S_3") (pintype "passive"))
      (node (ref "Q6") (pin "3") (pinfunction "S_3") (pintype "passive"))
    )
    (net (code "69") (name "Net-(Q6-D)") (class "Default")
      (node (ref "Q6") (pin "2") (pinfunction "D_2") (pintype "passive"))
      (node (ref "T5") (pin "E") (pinfunction "E_E") (pintype "passive"))
    )
    (net (code "70") (name "Net-(Q7-D)") (class "Default")
      (node (ref "Q7") (pin "1") (pinfunction "G_1") (pintype "passive"))
      (node (ref "Q7") (pin "2") (pinfunction "D_2") (pintype "passive"))
      (node (ref "Q8") (pin "1") (pinfunction "G_1") (pintype "passive"))
      (node (ref "T8") (pin "E") (pinfunction "E_E") (pintype "passive"))
    )
    (net (code "71") (name "Net-(Q7-S)") (class "Default")
      (node (ref "J26") (pin "1") (pinfunction "1_1") (pintype "passive"))
      (node (ref "Q7") (pin "3") (pinfunction "S_3") (pintype "passive"))
      (node (ref "Q8") (pin "3") (pinfunction "S_3") (pintype "passive"))
    )
    (net (code "72") (name "Net-(Q8-D)") (class "Default")
      (node (ref "Q8") (pin "2") (pinfunction "D_2") (pintype "passive"))
      (node (ref "T7") (pin "E") (pinfunction "E_E") (pintype "passive"))
    )
    (net (code "73") (name "Net-(Q10-D)") (class "Default")
      (node (ref "Q10") (pin "2") (pinfunction "D_2") (pintype "passive"))
      (node (ref "T9") (pin "E") (pinfunction "E_E") (pintype "passive"))
    )
    (net (code "74") (name "Net-(Q10-G)") (class "Default")
      (node (ref "Q10") (pin "1") (pinfunction "G_1") (pintype "passive"))
      (node (ref "Q9") (pin "1") (pinfunction "G_1") (pintype "passive"))
      (node (ref "Q9") (pin "2") (pinfunction "D_2") (pintype "passive"))
      (node (ref "T10") (pin "E") (pinfunction "E_E") (pintype "passive"))
    )
    (net (code "75") (name "Net-(Q10-S)") (class "Default")
      (node (ref "J34") (pin "1") (pinfunction "1_1") (pintype "passive"))
      (node (ref "Q10") (pin "3") (pinfunction "S_3") (pintype "passive"))
      (node (ref "Q9") (pin "3") (pinfunction "S_3") (pintype "passive"))
    )
    (net (code "76") (name "Net-(Q11-D)") (class "Default")
      (node (ref "Q11") (pin "1") (pinfunction "G_1") (pintype "passive"))
      (node (ref "Q11") (pin "2") (pinfunction "D_2") (pintype "passive"))
      (node (ref "Q12") (pin "1") (pinfunction "G_1") (pintype "passive"))
      (node (ref "T12") (pin "E") (pinfunction "E_E") (pintype "passive"))
    )
    (net (code "77") (name "Net-(Q11-S)") (class "Default")
      (node (ref "J42") (pin "1") (pinfunction "1_1") (pintype "passive"))
      (node (ref "Q11") (pin "3") (pinfunction "S_3") (pintype "passive"))
      (node (ref "Q12") (pin "3") (pinfunction "S_3") (pintype "passive"))
    )
    (net (code "78") (name "Net-(Q12-D)") (class "Default")
      (node (ref "Q12") (pin "2") (pinfunction "D_2") (pintype "passive"))
      (node (ref "T11") (pin "E") (pinfunction "E_E") (pintype "passive"))
    )
    (net (code "79") (name "Net-(Q13-D)") (class "Default")
      (node (ref "Q13") (pin "1") (pinfunction "G_1") (pintype "passive"))
      (node (ref "Q13") (pin "2") (pinfunction "D_2") (pintype "passive"))
      (node (ref "Q14") (pin "1") (pinfunction "G_1") (pintype "passive"))
      (node (ref "T14") (pin "E") (pinfunction "E_E") (pintype "passive"))
    )
    (net (code "80") (name "Net-(Q13-S)") (class "Default")
      (node (ref "J50") (pin "1") (pinfunction "1_1") (pintype "passive"))
      (node (ref "Q13") (pin "3") (pinfunction "S_3") (pintype "passive"))
      (node (ref "Q14") (pin "3") (pinfunction "S_3") (pintype "passive"))
    )
    (net (code "81") (name "Net-(Q14-D)") (class "Default")
      (node (ref "Q14") (pin "2") (pinfunction "D_2") (pintype "passive"))
      (node (ref "T13") (pin "E") (pinfunction "E_E") (pintype "passive"))
    )
    (net (code "82") (name "Net-(Q15-D)") (class "Default")
      (node (ref "Q15") (pin "1") (pinfunction "G_1") (pintype "passive"))
      (node (ref "Q15") (pin "2") (pinfunction "D_2") (pintype "passive"))
      (node (ref "Q16") (pin "1") (pinfunction "G_1") (pintype "passive"))
      (node (ref "T16") (pin "E") (pinfunction "E_E") (pintype "passive"))
    )
    (net (code "83") (name "Net-(Q15-S)") (class "Default")
      (node (ref "J58") (pin "1") (pinfunction "1_1") (pintype "passive"))
      (node (ref "Q15") (pin "3") (pinfunction "S_3") (pintype "passive"))
      (node (ref "Q16") (pin "3") (pinfunction "S_3") (pintype "passive"))
    )
    (net (code "84") (name "Net-(Q16-D)") (class "Default")
      (node (ref "Q16") (pin "2") (pinfunction "D_2") (pintype "passive"))
      (node (ref "T15") (pin "E") (pinfunction "E_E") (pintype "passive"))
    )
    (net (code "85") (name "Net-(Q17-D)") (class "Default")
      (node (ref "Q17") (pin "1") (pinfunction "G_1") (pintype "passive"))
      (node (ref "Q17") (pin "2") (pinfunction "D_2") (pintype "passive"))
      (node (ref "Q18") (pin "1") (pinfunction "G_1") (pintype "passive"))
      (node (ref "T18") (pin "E") (pinfunction "E_E") (pintype "passive"))
    )
    (net (code "86") (name "Net-(Q17-S)") (class "Default")
      (node (ref "J66") (pin "1") (pinfunction "1_1") (pintype "passive"))
      (node (ref "Q17") (pin "3") (pinfunction "S_3") (pintype "passive"))
      (node (ref "Q18") (pin "3") (pinfunction "S_3") (pintype "passive"))
    )
    (net (code "87") (name "Net-(Q18-D)") (class "Default")
      (node (ref "Q18") (pin "2") (pinfunction "D_2") (pintype "passive"))
      (node (ref "T17") (pin "E") (pinfunction "E_E") (pintype "passive"))
    )
    (net (code "88") (name "Net-(Q19-D)") (class "Default")
      (node (ref "Q19") (pin "1") (pinfunction "G_1") (pintype "passive"))
      (node (ref "Q19") (pin "2") (pinfunction "D_2") (pintype "passive"))
      (node (ref "Q20") (pin "1") (pinfunction "G_1") (pintype "passive"))
      (node (ref "T20") (pin "E") (pinfunction "E_E") (pintype "passive"))
    )
    (net (code "89") (name "Net-(Q19-S)") (class "Default")
      (node (ref "J74") (pin "1") (pinfunction "1_1") (pintype "passive"))
      (node (ref "Q19") (pin "3") (pinfunction "S_3") (pintype "passive"))
      (node (ref "Q20") (pin "3") (pinfunction "S_3") (pintype "passive"))
    )
    (net (code "90") (name "Net-(Q20-D)") (class "Default")
      (node (ref "Q20") (pin "2") (pinfunction "D_2") (pintype "passive"))
      (node (ref "T19") (pin "E") (pinfunction "E_E") (pintype "passive"))
    )
    (net (code "91") (name "Net-(Q21-D)") (class "Default")
      (node (ref "Q21") (pin "1") (pinfunction "G_1") (pintype "passive"))
      (node (ref "Q21") (pin "2") (pinfunction "D_2") (pintype "passive"))
      (node (ref "Q22") (pin "1") (pinfunction "G_1") (pintype "passive"))
      (node (ref "T22") (pin "E") (pinfunction "E_E") (pintype "passive"))
    )
    (net (code "92") (name "Net-(Q21-S)") (class "Default")
      (node (ref "J82") (pin "1") (pinfunction "1_1") (pintype "passive"))
      (node (ref "Q21") (pin "3") (pinfunction "S_3") (pintype "passive"))
      (node (ref "Q22") (pin "3") (pinfunction "S_3") (pintype "passive"))
    )
    (net (code "93") (name "Net-(Q22-D)") (class "Default")
      (node (ref "Q22") (pin "2") (pinfunction "D_2") (pintype "passive"))
      (node (ref "T21") (pin "E") (pinfunction "E_E") (pintype "passive"))
    )
    (net (code "94") (name "Net-(Q23-D)") (class "Default")
      (node (ref "Q23") (pin "1") (pinfunction "G_1") (pintype "passive"))
      (node (ref "Q23") (pin "2") (pinfunction "D_2") (pintype "passive"))
      (node (ref "Q24") (pin "1") (pinfunction "G_1") (pintype "passive"))
      (node (ref "T24") (pin "E") (pinfunction "E_E") (pintype "passive"))
    )
    (net (code "95") (name "Net-(Q23-S)") (class "Default")
      (node (ref "J90") (pin "1") (pinfunction "1_1") (pintype "passive"))
      (node (ref "Q23") (pin "3") (pinfunction "S_3") (pintype "passive"))
      (node (ref "Q24") (pin "3") (pinfunction "S_3") (pintype "passive"))
    )
    (net (code "96") (name "Net-(Q24-D)") (class "Default")
      (node (ref "Q24") (pin "2") (pinfunction "D_2") (pintype "passive"))
      (node (ref "T23") (pin "E") (pinfunction "E_E") (pintype "passive"))
    )
    (net (code "97") (name "Net-(R1-1)") (class "Default")
      (node (ref "J8") (pin "1") (pinfunction "1_1") (pintype "passive"))
      (node (ref "R1") (pin "P$1") (pinfunction "1_P$1") (pintype "passive"))
    )
    (net (code "98") (name "Net-(R1-2)") (class "Default")
      (node (ref "C1") (pin "2") (pinfunction "2_2") (pintype "passive"))
      (node (ref "R1") (pin "P$2") (pinfunction "2_P$2") (pintype "passive"))
      (node (ref "R2") (pin "P$1") (pinfunction "1_P$1") (pintype "passive"))
    )
    (net (code "99") (name "Net-(R2-2)") (class "Default")
      (node (ref "C2") (pin "1") (pinfunction "1_1") (pintype "passive"))
      (node (ref "LM324N") (pin "3") (pinfunction "3_3") (pintype "passive"))
      (node (ref "R2") (pin "P$2") (pinfunction "2_P$2") (pintype "passive"))
    )
    (net (code "100") (name "Net-(R3-1)") (class "Default")
      (node (ref "J1") (pin "1") (pinfunction "1_1") (pintype "passive"))
      (node (ref "R3") (pin "P$1") (pinfunction "1_P$1") (pintype "passive"))
      (node (ref "T1") (pin "C") (pinfunction "C_C") (pintype "passive"))
      (node (ref "T2") (pin "C") (pinfunction "C_C") (pintype "passive"))
    )
    (net (code "101") (name "Net-(R3-2)") (class "Default")
      (node (ref "J7") (pin "1") (pinfunction "1_1") (pintype "passive"))
      (node (ref "R3") (pin "P$2") (pinfunction "2_P$2") (pintype "passive"))
    )
    (net (code "102") (name "Net-(R4-1)") (class "Default")
      (node (ref "J13") (pin "1") (pinfunction "1_1") (pintype "passive"))
      (node (ref "R4") (pin "P$1") (pinfunction "1_P$1") (pintype "passive"))
    )
    (net (code "103") (name "Net-(R4-2)") (class "Default")
      (node (ref "C3") (pin "2") (pinfunction "2_2") (pintype "passive"))
      (node (ref "R4") (pin "P$2") (pinfunction "2_P$2") (pintype "passive"))
      (node (ref "R5") (pin "P$1") (pinfunction "1_P$1") (pintype "passive"))
    )
    (net (code "104") (name "Net-(R5-2)") (class "Default")
      (node (ref "C4") (pin "1") (pinfunction "1_1") (pintype "passive"))
      (node (ref "LM324N1") (pin "3") (pinfunction "3_3") (pintype "passive"))
      (node (ref "R5") (pin "P$2") (pinfunction "2_P$2") (pintype "passive"))
    )
    (net (code "105") (name "Net-(R6-1)") (class "Default")
      (node (ref "J2") (pin "1") (pinfunction "1_1") (pintype "passive"))
      (node (ref "R6") (pin "P$1") (pinfunction "1_P$1") (pintype "passive"))
      (node (ref "T3") (pin "C") (pinfunction "C_C") (pintype "passive"))
      (node (ref "T4") (pin "C") (pinfunction "C_C") (pintype "passive"))
    )
    (net (code "106") (name "Net-(R6-2)") (class "Default")
      (node (ref "J12") (pin "1") (pinfunction "1_1") (pintype "passive"))
      (node (ref "R6") (pin "P$2") (pinfunction "2_P$2") (pintype "passive"))
    )
    (net (code "107") (name "Net-(R7-1)") (class "Default")
      (node (ref "J21") (pin "1") (pinfunction "1_1") (pintype "passive"))
      (node (ref "R7") (pin "P$1") (pinfunction "1_P$1") (pintype "passive"))
    )
    (net (code "108") (name "Net-(R7-2)") (class "Default")
      (node (ref "C5") (pin "2") (pinfunction "2_2") (pintype "passive"))
      (node (ref "R7") (pin "P$2") (pinfunction "2_P$2") (pintype "passive"))
      (node (ref "R8") (pin "P$1") (pinfunction "1_P$1") (pintype "passive"))
    )
    (net (code "109") (name "Net-(R8-2)") (class "Default")
      (node (ref "C6") (pin "1") (pinfunction "1_1") (pintype "passive"))
      (node (ref "LM324N2") (pin "3") (pinfunction "3_3") (pintype "passive"))
      (node (ref "R8") (pin "P$2") (pinfunction "2_P$2") (pintype "passive"))
    )
    (net (code "110") (name "Net-(R9-1)") (class "Default")
      (node (ref "J17") (pin "1") (pinfunction "1_1") (pintype "passive"))
      (node (ref "R9") (pin "P$1") (pinfunction "1_P$1") (pintype "passive"))
      (node (ref "T5") (pin "C") (pinfunction "C_C") (pintype "passive"))
      (node (ref "T6") (pin "C") (pinfunction "C_C") (pintype "passive"))
    )
    (net (code "111") (name "Net-(R9-2)") (class "Default")
      (node (ref "J20") (pin "1") (pinfunction "1_1") (pintype "passive"))
      (node (ref "R9") (pin "P$2") (pinfunction "2_P$2") (pintype "passive"))
    )
    (net (code "112") (name "Net-(R10-1)") (class "Default")
      (node (ref "J29") (pin "1") (pinfunction "1_1") (pintype "passive"))
      (node (ref "R10") (pin "P$1") (pinfunction "1_P$1") (pintype "passive"))
    )
    (net (code "113") (name "Net-(R10-2)") (class "Default")
      (node (ref "C7") (pin "2") (pinfunction "2_2") (pintype "passive"))
      (node (ref "R10") (pin "P$2") (pinfunction "2_P$2") (pintype "passive"))
      (node (ref "R11") (pin "P$1") (pinfunction "1_P$1") (pintype "passive"))
    )
    (net (code "114") (name "Net-(R11-2)") (class "Default")
      (node (ref "C8") (pin "1") (pinfunction "1_1") (pintype "passive"))
      (node (ref "LM324N3") (pin "3") (pinfunction "3_3") (pintype "passive"))
      (node (ref "R11") (pin "P$2") (pinfunction "2_P$2") (pintype "passive"))
    )
    (net (code "115") (name "Net-(R12-1)") (class "Default")
      (node (ref "J25") (pin "1") (pinfunction "1_1") (pintype "passive"))
      (node (ref "R12") (pin "P$1") (pinfunction "1_P$1") (pintype "passive"))
      (node (ref "T7") (pin "C") (pinfunction "C_C") (pintype "passive"))
      (node (ref "T8") (pin "C") (pinfunction "C_C") (pintype "passive"))
    )
    (net (code "116") (name "Net-(R12-2)") (class "Default")
      (node (ref "J28") (pin "1") (pinfunction "1_1") (pintype "passive"))
      (node (ref "R12") (pin "P$2") (pinfunction "2_P$2") (pintype "passive"))
    )
    (net (code "117") (name "Net-(R13-1)") (class "Default")
      (node (ref "J37") (pin "1") (pinfunction "1_1") (pintype "passive"))
      (node (ref "R13") (pin "P$1") (pinfunction "1_P$1") (pintype "passive"))
    )
    (net (code "118") (name "Net-(R13-2)") (class "Default")
      (node (ref "C9") (pin "2") (pinfunction "2_2") (pintype "passive"))
      (node (ref "R13") (pin "P$2") (pinfunction "2_P$2") (pintype "passive"))
      (node (ref "R14") (pin "P$1") (pinfunction "1_P$1") (pintype "passive"))
    )
    (net (code "119") (name "Net-(R14-2)") (class "Default")
      (node (ref "C10") (pin "1") (pinfunction "1_1") (pintype "passive"))
      (node (ref "LM324N4") (pin "3") (pinfunction "3_3") (pintype "passive"))
      (node (ref "R14") (pin "P$2") (pinfunction "2_P$2") (pintype "passive"))
    )
    (net (code "120") (name "Net-(R15-1)") (class "Default")
      (node (ref "J33") (pin "1") (pinfunction "1_1") (pintype "passive"))
      (node (ref "R15") (pin "P$1") (pinfunction "1_P$1") (pintype "passive"))
      (node (ref "T10") (pin "C") (pinfunction "C_C") (pintype "passive"))
      (node (ref "T9") (pin "C") (pinfunction "C_C") (pintype "passive"))
    )
    (net (code "121") (name "Net-(R15-2)") (class "Default")
      (node (ref "J36") (pin "1") (pinfunction "1_1") (pintype "passive"))
      (node (ref "R15") (pin "P$2") (pinfunction "2_P$2") (pintype "passive"))
    )
    (net (code "122") (name "Net-(R16-1)") (class "Default")
      (node (ref "J45") (pin "1") (pinfunction "1_1") (pintype "passive"))
      (node (ref "R16") (pin "P$1") (pinfunction "1_P$1") (pintype "passive"))
    )
    (net (code "123") (name "Net-(R16-2)") (class "Default")
      (node (ref "C11") (pin "2") (pinfunction "2_2") (pintype "passive"))
      (node (ref "R16") (pin "P$2") (pinfunction "2_P$2") (pintype "passive"))
      (node (ref "R17") (pin "P$1") (pinfunction "1_P$1") (pintype "passive"))
    )
    (net (code "124") (name "Net-(R17-2)") (class "Default")
      (node (ref "C12") (pin "1") (pinfunction "1_1") (pintype "passive"))
      (node (ref "LM324N5") (pin "3") (pinfunction "3_3") (pintype "passive"))
      (node (ref "R17") (pin "P$2") (pinfunction "2_P$2") (pintype "passive"))
    )
    (net (code "125") (name "Net-(R18-1)") (class "Default")
      (node (ref "J41") (pin "1") (pinfunction "1_1") (pintype "passive"))
      (node (ref "R18") (pin "P$1") (pinfunction "1_P$1") (pintype "passive"))
      (node (ref "T11") (pin "C") (pinfunction "C_C") (pintype "passive"))
      (node (ref "T12") (pin "C") (pinfunction "C_C") (pintype "passive"))
    )
    (net (code "126") (name "Net-(R18-2)") (class "Default")
      (node (ref "J44") (pin "1") (pinfunction "1_1") (pintype "passive"))
      (node (ref "R18") (pin "P$2") (pinfunction "2_P$2") (pintype "passive"))
    )
    (net (code "127") (name "Net-(R19-1)") (class "Default")
      (node (ref "J53") (pin "1") (pinfunction "1_1") (pintype "passive"))
      (node (ref "R19") (pin "P$1") (pinfunction "1_P$1") (pintype "passive"))
    )
    (net (code "128") (name "Net-(R19-2)") (class "Default")
      (node (ref "C13") (pin "2") (pinfunction "2_2") (pintype "passive"))
      (node (ref "R19") (pin "P$2") (pinfunction "2_P$2") (pintype "passive"))
      (node (ref "R20") (pin "P$1") (pinfunction "1_P$1") (pintype "passive"))
    )
    (net (code "129") (name "Net-(R20-2)") (class "Default")
      (node (ref "C14") (pin "1") (pinfunction "1_1") (pintype "passive"))
      (node (ref "LM324N6") (pin "3") (pinfunction "3_3") (pintype "passive"))
      (node (ref "R20") (pin "P$2") (pinfunction "2_P$2") (pintype "passive"))
    )
    (net (code "130") (name "Net-(R21-1)") (class "Default")
      (node (ref "J49") (pin "1") (pinfunction "1_1") (pintype "passive"))
      (node (ref "R21") (pin "P$1") (pinfunction "1_P$1") (pintype "passive"))
      (node (ref "T13") (pin "C") (pinfunction "C_C") (pintype "passive"))
      (node (ref "T14") (pin "C") (pinfunction "C_C") (pintype "passive"))
    )
    (net (code "131") (name "Net-(R21-2)") (class "Default")
      (node (ref "J52") (pin "1") (pinfunction "1_1") (pintype "passive"))
      (node (ref "R21") (pin "P$2") (pinfunction "2_P$2") (pintype "passive"))
    )
    (net (code "132") (name "Net-(R22-1)") (class "Default")
      (node (ref "J61") (pin "1") (pinfunction "1_1") (pintype "passive"))
      (node (ref "R22") (pin "P$1") (pinfunction "1_P$1") (pintype "passive"))
    )
    (net (code "133") (name "Net-(R22-2)") (class "Default")
      (node (ref "C15") (pin "2") (pinfunction "2_2") (pintype "passive"))
      (node (ref "R22") (pin "P$2") (pinfunction "2_P$2") (pintype "passive"))
      (node (ref "R23") (pin "P$1") (pinfunction "1_P$1") (pintype "passive"))
    )
    (net (code "134") (name "Net-(R23-2)") (class "Default")
      (node (ref "C16") (pin "1") (pinfunction "1_1") (pintype "passive"))
      (node (ref "LM324N7") (pin "3") (pinfunction "3_3") (pintype "passive"))
      (node (ref "R23") (pin "P$2") (pinfunction "2_P$2") (pintype "passive"))
    )
    (net (code "135") (name "Net-(R24-1)") (class "Default")
      (node (ref "J57") (pin "1") (pinfunction "1_1") (pintype "passive"))
      (node (ref "R24") (pin "P$1") (pinfunction "1_P$1") (pintype "passive"))
      (node (ref "T15") (pin "C") (pinfunction "C_C") (pintype "passive"))
      (node (ref "T16") (pin "C") (pinfunction "C_C") (pintype "passive"))
    )
    (net (code "136") (name "Net-(R24-2)") (class "Default")
      (node (ref "J60") (pin "1") (pinfunction "1_1") (pintype "passive"))
      (node (ref "R24") (pin "P$2") (pinfunction "2_P$2") (pintype "passive"))
    )
    (net (code "137") (name "Net-(R25-1)") (class "Default")
      (node (ref "J69") (pin "1") (pinfunction "1_1") (pintype "passive"))
      (node (ref "R25") (pin "P$1") (pinfunction "1_P$1") (pintype "passive"))
    )
    (net (code "138") (name "Net-(R25-2)") (class "Default")
      (node (ref "C17") (pin "2") (pinfunction "2_2") (pintype "passive"))
      (node (ref "R25") (pin "P$2") (pinfunction "2_P$2") (pintype "passive"))
      (node (ref "R26") (pin "P$1") (pinfunction "1_P$1") (pintype "passive"))
    )
    (net (code "139") (name "Net-(R26-2)") (class "Default")
      (node (ref "C18") (pin "1") (pinfunction "1_1") (pintype "passive"))
      (node (ref "LM324N8") (pin "3") (pinfunction "3_3") (pintype "passive"))
      (node (ref "R26") (pin "P$2") (pinfunction "2_P$2") (pintype "passive"))
    )
    (net (code "140") (name "Net-(R27-1)") (class "Default")
      (node (ref "J65") (pin "1") (pinfunction "1_1") (pintype "passive"))
      (node (ref "R27") (pin "P$1") (pinfunction "1_P$1") (pintype "passive"))
      (node (ref "T17") (pin "C") (pinfunction "C_C") (pintype "passive"))
      (node (ref "T18") (pin "C") (pinfunction "C_C") (pintype "passive"))
    )
    (net (code "141") (name "Net-(R27-2)") (class "Default")
      (node (ref "J68") (pin "1") (pinfunction "1_1") (pintype "passive"))
      (node (ref "R27") (pin "P$2") (pinfunction "2_P$2") (pintype "passive"))
    )
    (net (code "142") (name "Net-(R28-1)") (class "Default")
      (node (ref "J77") (pin "1") (pinfunction "1_1") (pintype "passive"))
      (node (ref "R28") (pin "P$1") (pinfunction "1_P$1") (pintype "passive"))
    )
    (net (code "143") (name "Net-(R28-2)") (class "Default")
      (node (ref "C19") (pin "2") (pinfunction "2_2") (pintype "passive"))
      (node (ref "R28") (pin "P$2") (pinfunction "2_P$2") (pintype "passive"))
      (node (ref "R29") (pin "P$1") (pinfunction "1_P$1") (pintype "passive"))
    )
    (net (code "144") (name "Net-(R29-2)") (class "Default")
      (node (ref "C20") (pin "1") (pinfunction "1_1") (pintype "passive"))
      (node (ref "LM324N9") (pin "3") (pinfunction "3_3") (pintype "passive"))
      (node (ref "R29") (pin "P$2") (pinfunction "2_P$2") (pintype "passive"))
    )
    (net (code "145") (name "Net-(R30-1)") (class "Default")
      (node (ref "J73") (pin "1") (pinfunction "1_1") (pintype "passive"))
      (node (ref "R30") (pin "P$1") (pinfunction "1_P$1") (pintype "passive"))
      (node (ref "T19") (pin "C") (pinfunction "C_C") (pintype "passive"))
      (node (ref "T20") (pin "C") (pinfunction "C_C") (pintype "passive"))
    )
    (net (code "146") (name "Net-(R30-2)") (class "Default")
      (node (ref "J76") (pin "1") (pinfunction "1_1") (pintype "passive"))
      (node (ref "R30") (pin "P$2") (pinfunction "2_P$2") (pintype "passive"))
    )
    (net (code "147") (name "Net-(R31-1)") (class "Default")
      (node (ref "J85") (pin "1") (pinfunction "1_1") (pintype "passive"))
      (node (ref "R31") (pin "P$1") (pinfunction "1_P$1") (pintype "passive"))
    )
    (net (code "148") (name "Net-(R31-2)") (class "Default")
      (node (ref "C21") (pin "2") (pinfunction "2_2") (pintype "passive"))
      (node (ref "R31") (pin "P$2") (pinfunction "2_P$2") (pintype "passive"))
      (node (ref "R32") (pin "P$1") (pinfunction "1_P$1") (pintype "passive"))
    )
    (net (code "149") (name "Net-(R32-2)") (class "Default")
      (node (ref "C22") (pin "1") (pinfunction "1_1") (pintype "passive"))
      (node (ref "LM324N10") (pin "3") (pinfunction "3_3") (pintype "passive"))
      (node (ref "R32") (pin "P$2") (pinfunction "2_P$2") (pintype "passive"))
    )
    (net (code "150") (name "Net-(R33-1)") (class "Default")
      (node (ref "J81") (pin "1") (pinfunction "1_1") (pintype "passive"))
      (node (ref "R33") (pin "P$1") (pinfunction "1_P$1") (pintype "passive"))
      (node (ref "T21") (pin "C") (pinfunction "C_C") (pintype "passive"))
      (node (ref "T22") (pin "C") (pinfunction "C_C") (pintype "passive"))
    )
    (net (code "151") (name "Net-(R33-2)") (class "Default")
      (node (ref "J84") (pin "1") (pinfunction "1_1") (pintype "passive"))
      (node (ref "R33") (pin "P$2") (pinfunction "2_P$2") (pintype "passive"))
    )
    (net (code "152") (name "Net-(R34-1)") (class "Default")
      (node (ref "J93") (pin "1") (pinfunction "1_1") (pintype "passive"))
      (node (ref "R34") (pin "P$1") (pinfunction "1_P$1") (pintype "passive"))
    )
    (net (code "153") (name "Net-(R34-2)") (class "Default")
      (node (ref "C23") (pin "2") (pinfunction "2_2") (pintype "passive"))
      (node (ref "R34") (pin "P$2") (pinfunction "2_P$2") (pintype "passive"))
      (node (ref "R35") (pin "P$1") (pinfunction "1_P$1") (pintype "passive"))
    )
    (net (code "154") (name "Net-(R35-2)") (class "Default")
      (node (ref "C24") (pin "1") (pinfunction "1_1") (pintype "passive"))
      (node (ref "LM324N11") (pin "3") (pinfunction "3_3") (pintype "passive"))
      (node (ref "R35") (pin "P$2") (pinfunction "2_P$2") (pintype "passive"))
    )
    (net (code "155") (name "Net-(R36-1)") (class "Default")
      (node (ref "J89") (pin "1") (pinfunction "1_1") (pintype "passive"))
      (node (ref "R36") (pin "P$1") (pinfunction "1_P$1") (pintype "passive"))
      (node (ref "T23") (pin "C") (pinfunction "C_C") (pintype "passive"))
      (node (ref "T24") (pin "C") (pinfunction "C_C") (pintype "passive"))
    )
    (net (code "156") (name "Net-(R36-2)") (class "Default")
      (node (ref "J92") (pin "1") (pinfunction "1_1") (pintype "passive"))
      (node (ref "R36") (pin "P$2") (pinfunction "2_P$2") (pintype "passive"))
    )
    (net (code "157") (name "unconnected-(LM324N-Pad5)") (class "Default")
      (node (ref "LM324N") (pin "5") (pinfunction "5_5") (pintype "passive"))
    )
    (net (code "158") (name "unconnected-(LM324N-Pad6)") (class "Default")
      (node (ref "LM324N") (pin "6") (pinfunction "6_6") (pintype "passive"))
    )
    (net (code "159") (name "unconnected-(LM324N-Pad7)") (class "Default")
      (node (ref "LM324N") (pin "7") (pinfunction "7_7") (pintype "passive"))
    )
    (net (code "160") (name "unconnected-(LM324N-Pad8)") (class "Default")
      (node (ref "LM324N") (pin "8") (pinfunction "8_8") (pintype "passive"))
    )
    (net (code "161") (name "unconnected-(LM324N-Pad9)") (class "Default")
      (node (ref "LM324N") (pin "9") (pinfunction "9_9") (pintype "passive"))
    )
    (net (code "162") (name "unconnected-(LM324N-Pad10)") (class "Default")
      (node (ref "LM324N") (pin "10") (pinfunction "10_10") (pintype "passive"))
    )
    (net (code "163") (name "unconnected-(LM324N-Pad12)") (class "Default")
      (node (ref "LM324N") (pin "12") (pinfunction "12_12") (pintype "passive"))
    )
    (net (code "164") (name "unconnected-(LM324N-Pad13)") (class "Default")
      (node (ref "LM324N") (pin "13") (pinfunction "13_13") (pintype "passive"))
    )
    (net (code "165") (name "unconnected-(LM324N-Pad14)") (class "Default")
      (node (ref "LM324N") (pin "14") (pinfunction "14_14") (pintype "passive"))
    )
    (net (code "166") (name "unconnected-(LM324N1-Pad5)") (class "Default")
      (node (ref "LM324N1") (pin "5") (pinfunction "5_5") (pintype "passive"))
    )
    (net (code "167") (name "unconnected-(LM324N1-Pad6)") (class "Default")
      (node (ref "LM324N1") (pin "6") (pinfunction "6_6") (pintype "passive"))
    )
    (net (code "168") (name "unconnected-(LM324N1-Pad7)") (class "Default")
      (node (ref "LM324N1") (pin "7") (pinfunction "7_7") (pintype "passive"))
    )
    (net (code "169") (name "unconnected-(LM324N1-Pad8)") (class "Default")
      (node (ref "LM324N1") (pin "8") (pinfunction "8_8") (pintype "passive"))
    )
    (net (code "170") (name "unconnected-(LM324N1-Pad9)") (class "Default")
      (node (ref "LM324N1") (pin "9") (pinfunction "9_9") (pintype "passive"))
    )
    (net (code "171") (name "unconnected-(LM324N1-Pad10)") (class "Default")
      (node (ref "LM324N1") (pin "10") (pinfunction "10_10") (pintype "passive"))
    )
    (net (code "172") (name "unconnected-(LM324N1-Pad12)") (class "Default")
      (node (ref "LM324N1") (pin "12") (pinfunction "12_12") (pintype "passive"))
    )
    (net (code "173") (name "unconnected-(LM324N1-Pad13)") (class "Default")
      (node (ref "LM324N1") (pin "13") (pinfunction "13_13") (pintype "passive"))
    )
    (net (code "174") (name "unconnected-(LM324N1-Pad14)") (class "Default")
      (node (ref "LM324N1") (pin "14") (pinfunction "14_14") (pintype "passive"))
    )
    (net (code "175") (name "unconnected-(LM324N2-Pad5)") (class "Default")
      (node (ref "LM324N2") (pin "5") (pinfunction "5_5") (pintype "passive"))
    )
    (net (code "176") (name "unconnected-(LM324N2-Pad6)") (class "Default")
      (node (ref "LM324N2") (pin "6") (pinfunction "6_6") (pintype "passive"))
    )
    (net (code "177") (name "unconnected-(LM324N2-Pad7)") (class "Default")
      (node (ref "LM324N2") (pin "7") (pinfunction "7_7") (pintype "passive"))
    )
    (net (code "178") (name "unconnected-(LM324N2-Pad8)") (class "Default")
      (node (ref "LM324N2") (pin "8") (pinfunction "8_8") (pintype "passive"))
    )
    (net (code "179") (name "unconnected-(LM324N2-Pad9)") (class "Default")
      (node (ref "LM324N2") (pin "9") (pinfunction "9_9") (pintype "passive"))
    )
    (net (code "180") (name "unconnected-(LM324N2-Pad10)") (class "Default")
      (node (ref "LM324N2") (pin "10") (pinfunction "10_10") (pintype "passive"))
    )
    (net (code "181") (name "unconnected-(LM324N2-Pad12)") (class "Default")
      (node (ref "LM324N2") (pin "12") (pinfunction "12_12") (pintype "passive"))
    )
    (net (code "182") (name "unconnected-(LM324N2-Pad13)") (class "Default")
      (node (ref "LM324N2") (pin "13") (pinfunction "13_13") (pintype "passive"))
    )
    (net (code "183") (name "unconnected-(LM324N2-Pad14)") (class "Default")
      (node (ref "LM324N2") (pin "14") (pinfunction "14_14") (pintype "passive"))
    )
    (net (code "184") (name "unconnected-(LM324N3-Pad5)") (class "Default")
      (node (ref "LM324N3") (pin "5") (pinfunction "5_5") (pintype "passive"))
    )
    (net (code "185") (name "unconnected-(LM324N3-Pad6)") (class "Default")
      (node (ref "LM324N3") (pin "6") (pinfunction "6_6") (pintype "passive"))
    )
    (net (code "186") (name "unconnected-(LM324N3-Pad7)") (class "Default")
      (node (ref "LM324N3") (pin "7") (pinfunction "7_7") (pintype "passive"))
    )
    (net (code "187") (name "unconnected-(LM324N3-Pad8)") (class "Default")
      (node (ref "LM324N3") (pin "8") (pinfunction "8_8") (pintype "passive"))
    )
    (net (code "188") (name "unconnected-(LM324N3-Pad9)") (class "Default")
      (node (ref "LM324N3") (pin "9") (pinfunction "9_9") (pintype "passive"))
    )
    (net (code "189") (name "unconnected-(LM324N3-Pad10)") (class "Default")
      (node (ref "LM324N3") (pin "10") (pinfunction "10_10") (pintype "passive"))
    )
    (net (code "190") (name "unconnected-(LM324N3-Pad12)") (class "Default")
      (node (ref "LM324N3") (pin "12") (pinfunction "12_12") (pintype "passive"))
    )
    (net (code "191") (name "unconnected-(LM324N3-Pad13)") (class "Default")
      (node (ref "LM324N3") (pin "13") (pinfunction "13_13") (pintype "passive"))
    )
    (net (code "192") (name "unconnected-(LM324N3-Pad14)") (class "Default")
      (node (ref "LM324N3") (pin "14") (pinfunction "14_14") (pintype "passive"))
    )
    (net (code "193") (name "unconnected-(LM324N4-Pad5)") (class "Default")
      (node (ref "LM324N4") (pin "5") (pinfunction "5_5") (pintype "passive"))
    )
    (net (code "194") (name "unconnected-(LM324N4-Pad6)") (class "Default")
      (node (ref "LM324N4") (pin "6") (pinfunction "6_6") (pintype "passive"))
    )
    (net (code "195") (name "unconnected-(LM324N4-Pad7)") (class "Default")
      (node (ref "LM324N4") (pin "7") (pinfunction "7_7") (pintype "passive"))
    )
    (net (code "196") (name "unconnected-(LM324N4-Pad8)") (class "Default")
      (node (ref "LM324N4") (pin "8") (pinfunction "8_8") (pintype "passive"))
    )
    (net (code "197") (name "unconnected-(LM324N4-Pad9)") (class "Default")
      (node (ref "LM324N4") (pin "9") (pinfunction "9_9") (pintype "passive"))
    )
    (net (code "198") (name "unconnected-(LM324N4-Pad10)") (class "Default")
      (node (ref "LM324N4") (pin "10") (pinfunction "10_10") (pintype "passive"))
    )
    (net (code "199") (name "unconnected-(LM324N4-Pad12)") (class "Default")
      (node (ref "LM324N4") (pin "12") (pinfunction "12_12") (pintype "passive"))
    )
    (net (code "200") (name "unconnected-(LM324N4-Pad13)") (class "Default")
      (node (ref "LM324N4") (pin "13") (pinfunction "13_13") (pintype "passive"))
    )
    (net (code "201") (name "unconnected-(LM324N4-Pad14)") (class "Default")
      (node (ref "LM324N4") (pin "14") (pinfunction "14_14") (pintype "passive"))
    )
    (net (code "202") (name "unconnected-(LM324N5-Pad5)") (class "Default")
      (node (ref "LM324N5") (pin "5") (pinfunction "5_5") (pintype "passive"))
    )
    (net (code "203") (name "unconnected-(LM324N5-Pad6)") (class "Default")
      (node (ref "LM324N5") (pin "6") (pinfunction "6_6") (pintype "passive"))
    )
    (net (code "204") (name "unconnected-(LM324N5-Pad7)") (class "Default")
      (node (ref "LM324N5") (pin "7") (pinfunction "7_7") (pintype "passive"))
    )
    (net (code "205") (name "unconnected-(LM324N5-Pad8)") (class "Default")
      (node (ref "LM324N5") (pin "8") (pinfunction "8_8") (pintype "passive"))
    )
    (net (code "206") (name "unconnected-(LM324N5-Pad9)") (class "Default")
      (node (ref "LM324N5") (pin "9") (pinfunction "9_9") (pintype "passive"))
    )
    (net (code "207") (name "unconnected-(LM324N5-Pad10)") (class "Default")
      (node (ref "LM324N5") (pin "10") (pinfunction "10_10") (pintype "passive"))
    )
    (net (code "208") (name "unconnected-(LM324N5-Pad12)") (class "Default")
      (node (ref "LM324N5") (pin "12") (pinfunction "12_12") (pintype "passive"))
    )
    (net (code "209") (name "unconnected-(LM324N5-Pad13)") (class "Default")
      (node (ref "LM324N5") (pin "13") (pinfunction "13_13") (pintype "passive"))
    )
    (net (code "210") (name "unconnected-(LM324N5-Pad14)") (class "Default")
      (node (ref "LM324N5") (pin "14") (pinfunction "14_14") (pintype "passive"))
    )
    (net (code "211") (name "unconnected-(LM324N6-Pad5)") (class "Default")
      (node (ref "LM324N6") (pin "5") (pinfunction "5_5") (pintype "passive"))
    )
    (net (code "212") (name "unconnected-(LM324N6-Pad6)") (class "Default")
      (node (ref "LM324N6") (pin "6") (pinfunction "6_6") (pintype "passive"))
    )
    (net (code "213") (name "unconnected-(LM324N6-Pad7)") (class "Default")
      (node (ref "LM324N6") (pin "7") (pinfunction "7_7") (pintype "passive"))
    )
    (net (code "214") (name "unconnected-(LM324N6-Pad8)") (class "Default")
      (node (ref "LM324N6") (pin "8") (pinfunction "8_8") (pintype "passive"))
    )
    (net (code "215") (name "unconnected-(LM324N6-Pad9)") (class "Default")
      (node (ref "LM324N6") (pin "9") (pinfunction "9_9") (pintype "passive"))
    )
    (net (code "216") (name "unconnected-(LM324N6-Pad10)") (class "Default")
      (node (ref "LM324N6") (pin "10") (pinfunction "10_10") (pintype "passive"))
    )
    (net (code "217") (name "unconnected-(LM324N6-Pad12)") (class "Default")
      (node (ref "LM324N6") (pin "12") (pinfunction "12_12") (pintype "passive"))
    )
    (net (code "218") (name "unconnected-(LM324N6-Pad13)") (class "Default")
      (node (ref "LM324N6") (pin "13") (pinfunction "13_13") (pintype "passive"))
    )
    (net (code "219") (name "unconnected-(LM324N6-Pad14)") (class "Default")
      (node (ref "LM324N6") (pin "14") (pinfunction "14_14") (pintype "passive"))
    )
    (net (code "220") (name "unconnected-(LM324N7-Pad5)") (class "Default")
      (node (ref "LM324N7") (pin "5") (pinfunction "5_5") (pintype "passive"))
    )
    (net (code "221") (name "unconnected-(LM324N7-Pad6)") (class "Default")
      (node (ref "LM324N7") (pin "6") (pinfunction "6_6") (pintype "passive"))
    )
    (net (code "222") (name "unconnected-(LM324N7-Pad7)") (class "Default")
      (node (ref "LM324N7") (pin "7") (pinfunction "7_7") (pintype "passive"))
    )
    (net (code "223") (name "unconnected-(LM324N7-Pad8)") (class "Default")
      (node (ref "LM324N7") (pin "8") (pinfunction "8_8") (pintype "passive"))
    )
    (net (code "224") (name "unconnected-(LM324N7-Pad9)") (class "Default")
      (node (ref "LM324N7") (pin "9") (pinfunction "9_9") (pintype "passive"))
    )
    (net (code "225") (name "unconnected-(LM324N7-Pad10)") (class "Default")
      (node (ref "LM324N7") (pin "10") (pinfunction "10_10") (pintype "passive"))
    )
    (net (code "226") (name "unconnected-(LM324N7-Pad12)") (class "Default")
      (node (ref "LM324N7") (pin "12") (pinfunction "12_12") (pintype "passive"))
    )
    (net (code "227") (name "unconnected-(LM324N7-Pad13)") (class "Default")
      (node (ref "LM324N7") (pin "13") (pinfunction "13_13") (pintype "passive"))
    )
    (net (code "228") (name "unconnected-(LM324N7-Pad14)") (class "Default")
      (node (ref "LM324N7") (pin "14") (pinfunction "14_14") (pintype "passive"))
    )
    (net (code "229") (name "unconnected-(LM324N8-Pad5)") (class "Default")
      (node (ref "LM324N8") (pin "5") (pinfunction "5_5") (pintype "passive"))
    )
    (net (code "230") (name "unconnected-(LM324N8-Pad6)") (class "Default")
      (node (ref "LM324N8") (pin "6") (pinfunction "6_6") (pintype "passive"))
    )
    (net (code "231") (name "unconnected-(LM324N8-Pad7)") (class "Default")
      (node (ref "LM324N8") (pin "7") (pinfunction "7_7") (pintype "passive"))
    )
    (net (code "232") (name "unconnected-(LM324N8-Pad8)") (class "Default")
      (node (ref "LM324N8") (pin "8") (pinfunction "8_8") (pintype "passive"))
    )
    (net (code "233") (name "unconnected-(LM324N8-Pad9)") (class "Default")
      (node (ref "LM324N8") (pin "9") (pinfunction "9_9") (pintype "passive"))
    )
    (net (code "234") (name "unconnected-(LM324N8-Pad10)") (class "Default")
      (node (ref "LM324N8") (pin "10") (pinfunction "10_10") (pintype "passive"))
    )
    (net (code "235") (name "unconnected-(LM324N8-Pad12)") (class "Default")
      (node (ref "LM324N8") (pin "12") (pinfunction "12_12") (pintype "passive"))
    )
    (net (code "236") (name "unconnected-(LM324N8-Pad13)") (class "Default")
      (node (ref "LM324N8") (pin "13") (pinfunction "13_13") (pintype "passive"))
    )
    (net (code "237") (name "unconnected-(LM324N8-Pad14)") (class "Default")
      (node (ref "LM324N8") (pin "14") (pinfunction "14_14") (pintype "passive"))
    )
    (net (code "238") (name "unconnected-(LM324N9-Pad5)") (class "Default")
      (node (ref "LM324N9") (pin "5") (pinfunction "5_5") (pintype "passive"))
    )
    (net (code "239") (name "unconnected-(LM324N9-Pad6)") (class "Default")
      (node (ref "LM324N9") (pin "6") (pinfunction "6_6") (pintype "passive"))
    )
    (net (code "240") (name "unconnected-(LM324N9-Pad7)") (class "Default")
      (node (ref "LM324N9") (pin "7") (pinfunction "7_7") (pintype "passive"))
    )
    (net (code "241") (name "unconnected-(LM324N9-Pad8)") (class "Default")
      (node (ref "LM324N9") (pin "8") (pinfunction "8_8") (pintype "passive"))
    )
    (net (code "242") (name "unconnected-(LM324N9-Pad9)") (class "Default")
      (node (ref "LM324N9") (pin "9") (pinfunction "9_9") (pintype "passive"))
    )
    (net (code "243") (name "unconnected-(LM324N9-Pad10)") (class "Default")
      (node (ref "LM324N9") (pin "10") (pinfunction "10_10") (pintype "passive"))
    )
    (net (code "244") (name "unconnected-(LM324N9-Pad12)") (class "Default")
      (node (ref "LM324N9") (pin "12") (pinfunction "12_12") (pintype "passive"))
    )
    (net (code "245") (name "unconnected-(LM324N9-Pad13)") (class "Default")
      (node (ref "LM324N9") (pin "13") (pinfunction "13_13") (pintype "passive"))
    )
    (net (code "246") (name "unconnected-(LM324N9-Pad14)") (class "Default")
      (node (ref "LM324N9") (pin "14") (pinfunction "14_14") (pintype "passive"))
    )
    (net (code "247") (name "unconnected-(LM324N10-Pad5)") (class "Default")
      (node (ref "LM324N10") (pin "5") (pinfunction "5_5") (pintype "passive"))
    )
    (net (code "248") (name "unconnected-(LM324N10-Pad6)") (class "Default")
      (node (ref "LM324N10") (pin "6") (pinfunction "6_6") (pintype "passive"))
    )
    (net (code "249") (name "unconnected-(LM324N10-Pad7)") (class "Default")
      (node (ref "LM324N10") (pin "7") (pinfunction "7_7") (pintype "passive"))
    )
    (net (code "250") (name "unconnected-(LM324N10-Pad8)") (class "Default")
      (node (ref "LM324N10") (pin "8") (pinfunction "8_8") (pintype "passive"))
    )
    (net (code "251") (name "unconnected-(LM324N10-Pad9)") (class "Default")
      (node (ref "LM324N10") (pin "9") (pinfunction "9_9") (pintype "passive"))
    )
    (net (code "252") (name "unconnected-(LM324N10-Pad10)") (class "Default")
      (node (ref "LM324N10") (pin "10") (pinfunction "10_10") (pintype "passive"))
    )
    (net (code "253") (name "unconnected-(LM324N10-Pad12)") (class "Default")
      (node (ref "LM324N10") (pin "12") (pinfunction "12_12") (pintype "passive"))
    )
    (net (code "254") (name "unconnected-(LM324N10-Pad13)") (class "Default")
      (node (ref "LM324N10") (pin "13") (pinfunction "13_13") (pintype "passive"))
    )
    (net (code "255") (name "unconnected-(LM324N10-Pad14)") (class "Default")
      (node (ref "LM324N10") (pin "14") (pinfunction "14_14") (pintype "passive"))
    )
    (net (code "256") (name "unconnected-(LM324N11-Pad5)") (class "Default")
      (node (ref "LM324N11") (pin "5") (pinfunction "5_5") (pintype "passive"))
    )
    (net (code "257") (name "unconnected-(LM324N11-Pad6)") (class "Default")
      (node (ref "LM324N11") (pin "6") (pinfunction "6_6") (pintype "passive"))
    )
    (net (code "258") (name "unconnected-(LM324N11-Pad7)") (class "Default")
      (node (ref "LM324N11") (pin "7") (pinfunction "7_7") (pintype "passive"))
    )
    (net (code "259") (name "unconnected-(LM324N11-Pad8)") (class "Default")
      (node (ref "LM324N11") (pin "8") (pinfunction "8_8") (pintype "passive"))
    )
    (net (code "260") (name "unconnected-(LM324N11-Pad9)") (class "Default")
      (node (ref "LM324N11") (pin "9") (pinfunction "9_9") (pintype "passive"))
    )
    (net (code "261") (name "unconnected-(LM324N11-Pad10)") (class "Default")
      (node (ref "LM324N11") (pin "10") (pinfunction "10_10") (pintype "passive"))
    )
    (net (code "262") (name "unconnected-(LM324N11-Pad12)") (class "Default")
      (node (ref "LM324N11") (pin "12") (pinfunction "12_12") (pintype "passive"))
    )
    (net (code "263") (name "unconnected-(LM324N11-Pad13)") (class "Default")
      (node (ref "LM324N11") (pin "13") (pinfunction "13_13") (pintype "passive"))
    )
    (net (code "264") (name "unconnected-(LM324N11-Pad14)") (class "Default")
      (node (ref "LM324N11") (pin "14") (pinfunction "14_14") (pintype "passive"))
    )
  )
)
